# MusselGapeTracker_RevD.net
KiCad netlist of a schematic drawn in EAGLE
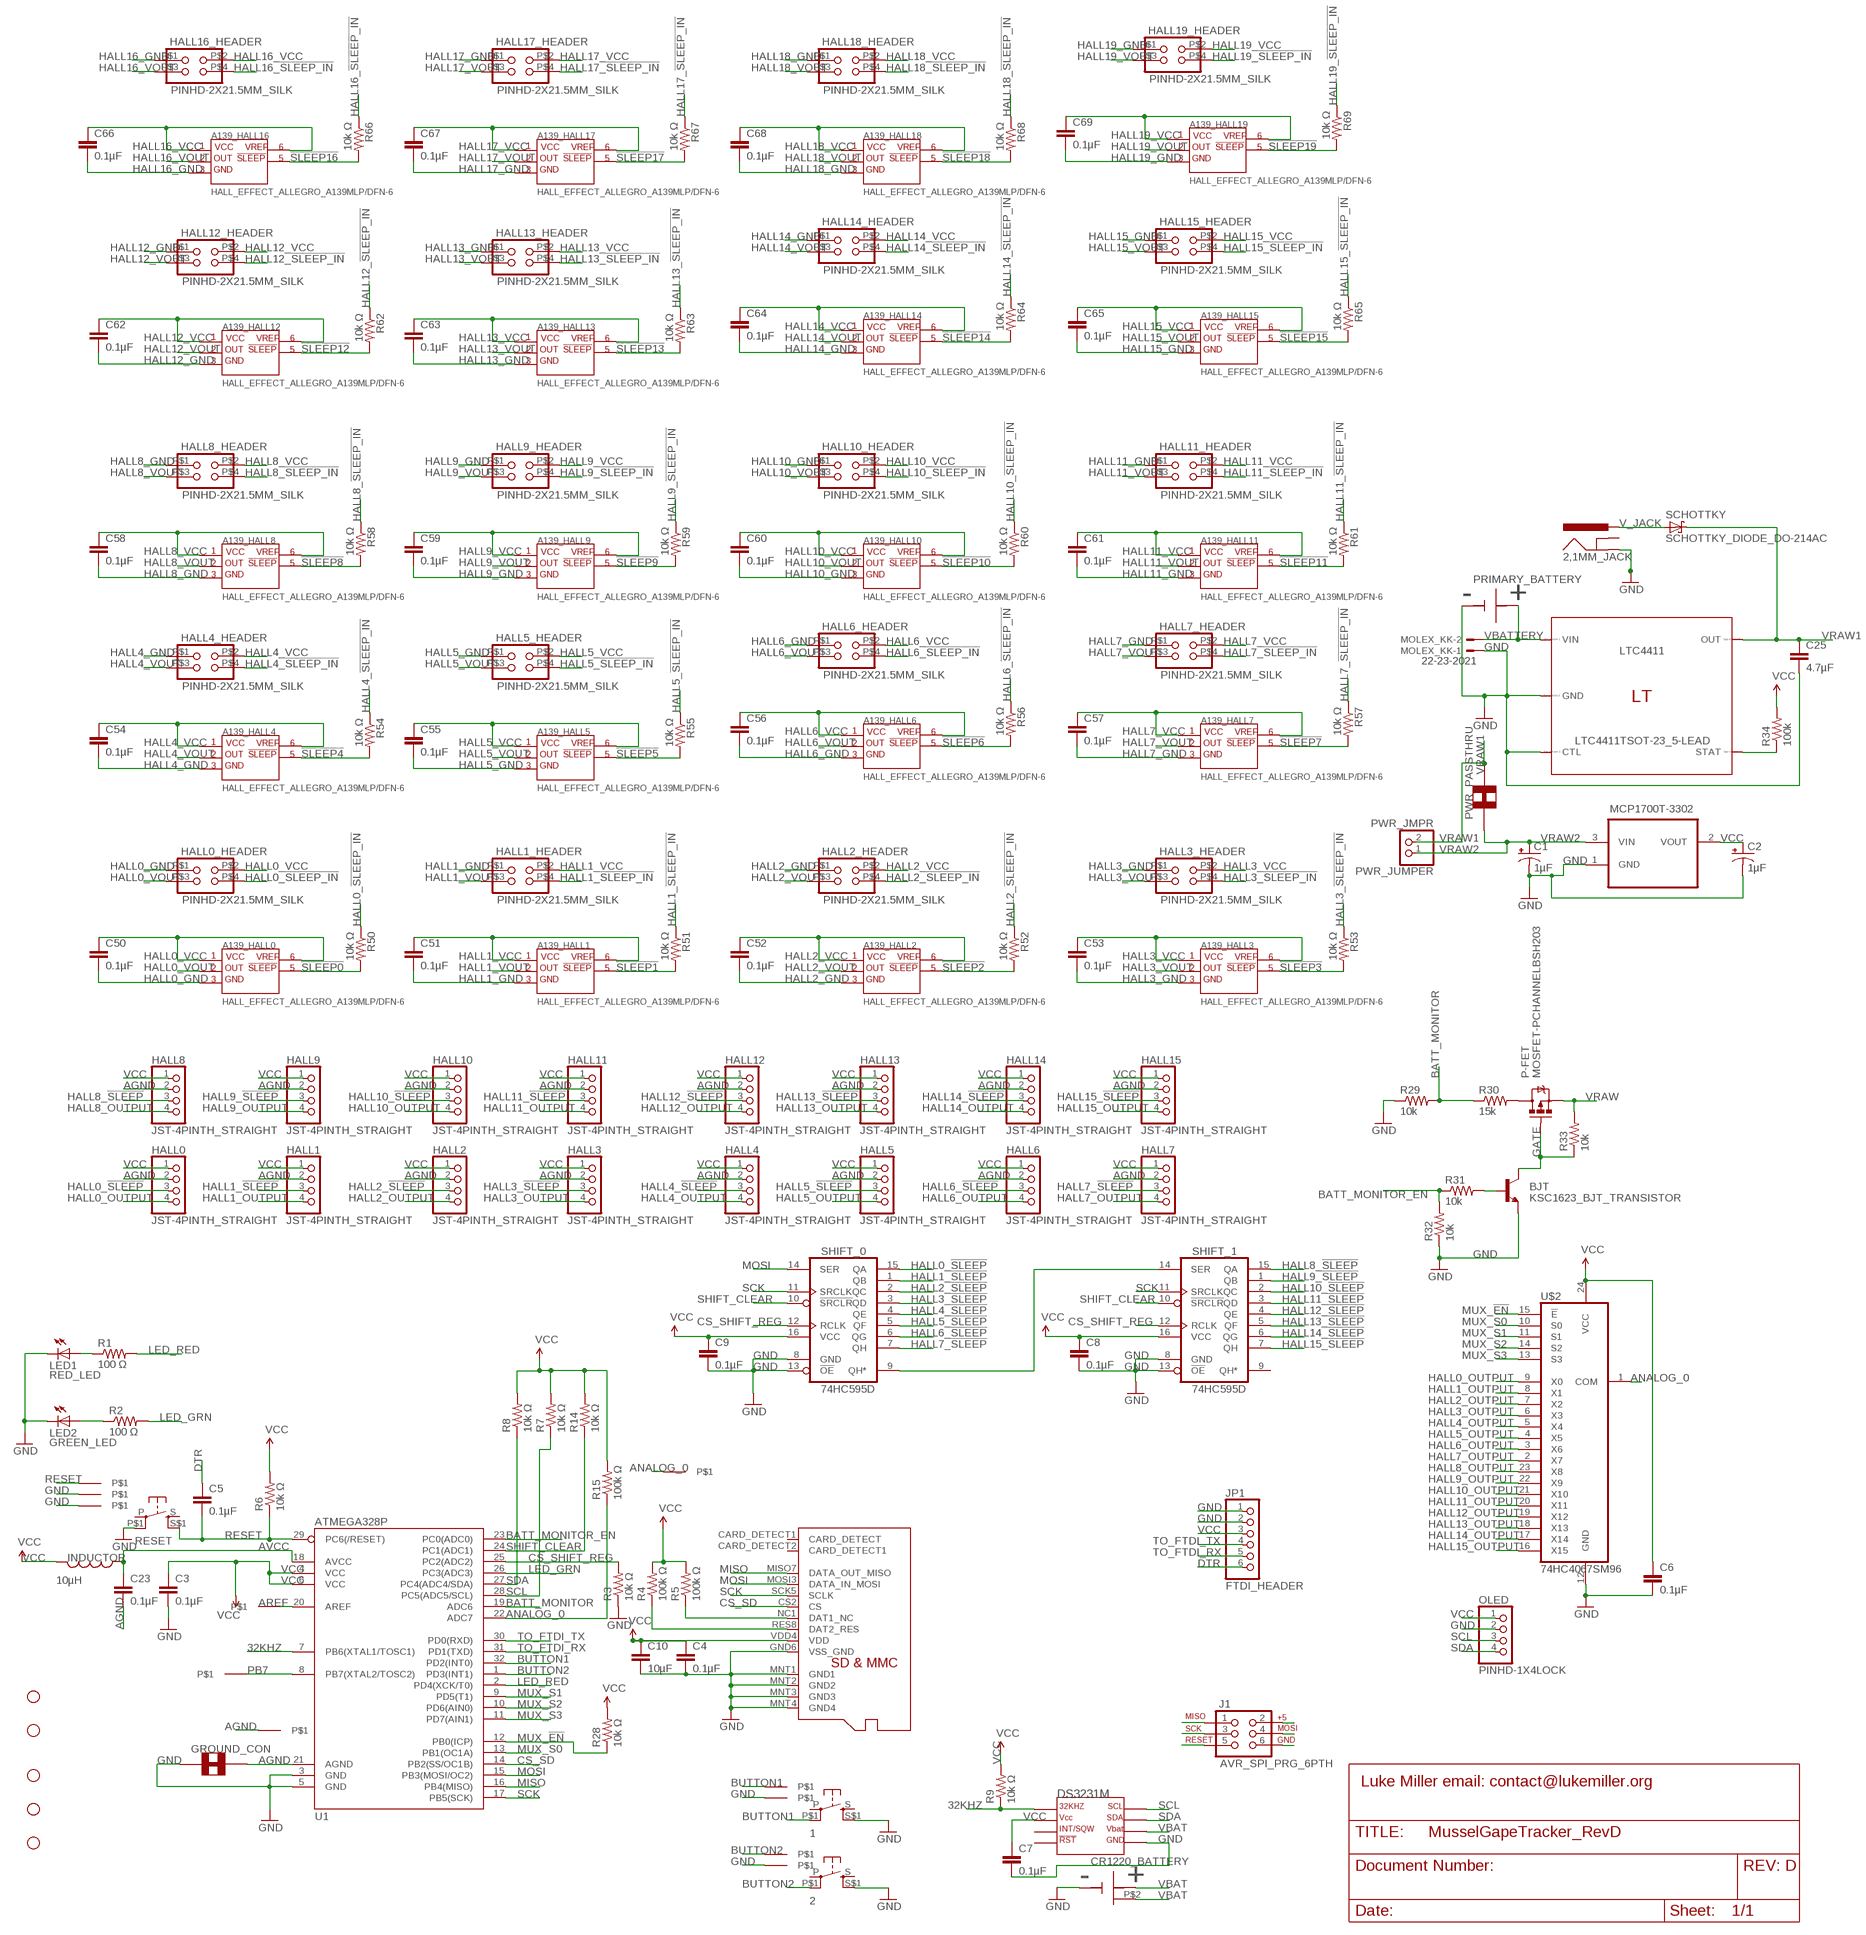
[diagram p0: schematic, sheet 1]

(export (version "E")
  (design (tool "Eeschema 10.0.6"))
  (components
    (comp (ref "1")
      (value "PUSHBUTTON_DPST_SMDSTANDARD")
      (footprint "eagle-import:PUSHBUTTON_DPST_SMD")
      (libsource (lib "eagle-import") (part "PUSHBUTTON_DPST_SMDSTANDARD"))
    )
    (comp (ref "2")
      (value "PUSHBUTTON_DPST_SMDSTANDARD")
      (footprint "eagle-import:PUSHBUTTON_DPST_SMD")
      (libsource (lib "eagle-import") (part "PUSHBUTTON_DPST_SMDSTANDARD"))
    )
    (comp (ref "2,1MM_JACK")
      (value "POWER_JACK_2,1MM")
      (footprint "eagle-import:POWER_JACK_DC_2,1MM")
      (libsource (lib "eagle-import") (part "POWER_JACK_2,1MM"))
    )
    (comp (ref "A139_HALL0")
      (value "HALL_EFFECT_ALLEGRO_A139MLP/DFN-6")
      (footprint "eagle-import:A139__HALL_EFFECT")
      (libsource (lib "eagle-import") (part "HALL_EFFECT_ALLEGRO_A139MLP/DFN-6"))
    )
    (comp (ref "A139_HALL1")
      (value "HALL_EFFECT_ALLEGRO_A139MLP/DFN-6")
      (footprint "eagle-import:A139__HALL_EFFECT")
      (libsource (lib "eagle-import") (part "HALL_EFFECT_ALLEGRO_A139MLP/DFN-6"))
    )
    (comp (ref "A139_HALL2")
      (value "HALL_EFFECT_ALLEGRO_A139MLP/DFN-6")
      (footprint "eagle-import:A139__HALL_EFFECT")
      (libsource (lib "eagle-import") (part "HALL_EFFECT_ALLEGRO_A139MLP/DFN-6"))
    )
    (comp (ref "A139_HALL3")
      (value "HALL_EFFECT_ALLEGRO_A139MLP/DFN-6")
      (footprint "eagle-import:A139__HALL_EFFECT")
      (libsource (lib "eagle-import") (part "HALL_EFFECT_ALLEGRO_A139MLP/DFN-6"))
    )
    (comp (ref "A139_HALL4")
      (value "HALL_EFFECT_ALLEGRO_A139MLP/DFN-6")
      (footprint "eagle-import:A139__HALL_EFFECT")
      (libsource (lib "eagle-import") (part "HALL_EFFECT_ALLEGRO_A139MLP/DFN-6"))
    )
    (comp (ref "A139_HALL5")
      (value "HALL_EFFECT_ALLEGRO_A139MLP/DFN-6")
      (footprint "eagle-import:A139__HALL_EFFECT")
      (libsource (lib "eagle-import") (part "HALL_EFFECT_ALLEGRO_A139MLP/DFN-6"))
    )
    (comp (ref "A139_HALL6")
      (value "HALL_EFFECT_ALLEGRO_A139MLP/DFN-6")
      (footprint "eagle-import:A139__HALL_EFFECT")
      (libsource (lib "eagle-import") (part "HALL_EFFECT_ALLEGRO_A139MLP/DFN-6"))
    )
    (comp (ref "A139_HALL7")
      (value "HALL_EFFECT_ALLEGRO_A139MLP/DFN-6")
      (footprint "eagle-import:A139__HALL_EFFECT")
      (libsource (lib "eagle-import") (part "HALL_EFFECT_ALLEGRO_A139MLP/DFN-6"))
    )
    (comp (ref "A139_HALL8")
      (value "HALL_EFFECT_ALLEGRO_A139MLP/DFN-6")
      (footprint "eagle-import:A139__HALL_EFFECT")
      (libsource (lib "eagle-import") (part "HALL_EFFECT_ALLEGRO_A139MLP/DFN-6"))
    )
    (comp (ref "A139_HALL9")
      (value "HALL_EFFECT_ALLEGRO_A139MLP/DFN-6")
      (footprint "eagle-import:A139__HALL_EFFECT")
      (libsource (lib "eagle-import") (part "HALL_EFFECT_ALLEGRO_A139MLP/DFN-6"))
    )
    (comp (ref "A139_HALL10")
      (value "HALL_EFFECT_ALLEGRO_A139MLP/DFN-6")
      (footprint "eagle-import:A139__HALL_EFFECT")
      (libsource (lib "eagle-import") (part "HALL_EFFECT_ALLEGRO_A139MLP/DFN-6"))
    )
    (comp (ref "A139_HALL11")
      (value "HALL_EFFECT_ALLEGRO_A139MLP/DFN-6")
      (footprint "eagle-import:A139__HALL_EFFECT")
      (libsource (lib "eagle-import") (part "HALL_EFFECT_ALLEGRO_A139MLP/DFN-6"))
    )
    (comp (ref "A139_HALL12")
      (value "HALL_EFFECT_ALLEGRO_A139MLP/DFN-6")
      (footprint "eagle-import:A139__HALL_EFFECT")
      (libsource (lib "eagle-import") (part "HALL_EFFECT_ALLEGRO_A139MLP/DFN-6"))
    )
    (comp (ref "A139_HALL13")
      (value "HALL_EFFECT_ALLEGRO_A139MLP/DFN-6")
      (footprint "eagle-import:A139__HALL_EFFECT")
      (libsource (lib "eagle-import") (part "HALL_EFFECT_ALLEGRO_A139MLP/DFN-6"))
    )
    (comp (ref "A139_HALL14")
      (value "HALL_EFFECT_ALLEGRO_A139MLP/DFN-6")
      (footprint "eagle-import:A139__HALL_EFFECT")
      (libsource (lib "eagle-import") (part "HALL_EFFECT_ALLEGRO_A139MLP/DFN-6"))
    )
    (comp (ref "A139_HALL15")
      (value "HALL_EFFECT_ALLEGRO_A139MLP/DFN-6")
      (footprint "eagle-import:A139__HALL_EFFECT")
      (libsource (lib "eagle-import") (part "HALL_EFFECT_ALLEGRO_A139MLP/DFN-6"))
    )
    (comp (ref "A139_HALL16")
      (value "HALL_EFFECT_ALLEGRO_A139MLP/DFN-6")
      (footprint "eagle-import:A139__HALL_EFFECT")
      (libsource (lib "eagle-import") (part "HALL_EFFECT_ALLEGRO_A139MLP/DFN-6"))
    )
    (comp (ref "A139_HALL17")
      (value "HALL_EFFECT_ALLEGRO_A139MLP/DFN-6")
      (footprint "eagle-import:A139__HALL_EFFECT")
      (libsource (lib "eagle-import") (part "HALL_EFFECT_ALLEGRO_A139MLP/DFN-6"))
    )
    (comp (ref "A139_HALL18")
      (value "HALL_EFFECT_ALLEGRO_A139MLP/DFN-6")
      (footprint "eagle-import:A139__HALL_EFFECT")
      (libsource (lib "eagle-import") (part "HALL_EFFECT_ALLEGRO_A139MLP/DFN-6"))
    )
    (comp (ref "A139_HALL19")
      (value "HALL_EFFECT_ALLEGRO_A139MLP/DFN-6")
      (footprint "eagle-import:A139__HALL_EFFECT")
      (libsource (lib "eagle-import") (part "HALL_EFFECT_ALLEGRO_A139MLP/DFN-6"))
    )
    (comp (ref "BJT")
      (value "KSC1623_BJT_TRANSISTOR")
      (footprint "eagle-import:SOT23")
      (libsource (lib "eagle-import") (part "KSC1623_BJT_TRANSISTOR"))
    )
    (comp (ref "C1")
      (value "1µF")
      (footprint "eagle-import:PANASONIC_B")
      (libsource (lib "eagle-import") (part "CPOL-USB"))
    )
    (comp (ref "C2")
      (value "1µF")
      (footprint "eagle-import:PANASONIC_B")
      (libsource (lib "eagle-import") (part "CPOL-USB"))
    )
    (comp (ref "C3")
      (value "0.1µF")
      (footprint "eagle-import:0603")
      (libsource (lib "eagle-import") (part "CAP0603"))
    )
    (comp (ref "C4")
      (value "0.1µF")
      (footprint "eagle-import:0603")
      (libsource (lib "eagle-import") (part "CAP0603"))
    )
    (comp (ref "C5")
      (value "0.1µF")
      (footprint "eagle-import:0603")
      (libsource (lib "eagle-import") (part "CAP0603"))
    )
    (comp (ref "C6")
      (value "0.1µF")
      (footprint "eagle-import:0603")
      (libsource (lib "eagle-import") (part "CAP0603"))
    )
    (comp (ref "C7")
      (value "0.1µF")
      (footprint "eagle-import:0603")
      (libsource (lib "eagle-import") (part "CAP0603"))
    )
    (comp (ref "C8")
      (value "0.1µF")
      (footprint "eagle-import:0603")
      (libsource (lib "eagle-import") (part "CAP0603"))
    )
    (comp (ref "C9")
      (value "0.1µF")
      (footprint "eagle-import:0603")
      (libsource (lib "eagle-import") (part "CAP0603"))
    )
    (comp (ref "C10")
      (value "10µF")
      (footprint "eagle-import:0603")
      (libsource (lib "eagle-import") (part "CAP0603"))
    )
    (comp (ref "C23")
      (value "0.1µF")
      (footprint "eagle-import:0603")
      (libsource (lib "eagle-import") (part "CAP0603"))
    )
    (comp (ref "C25")
      (value "4.7µF")
      (footprint "eagle-import:0603")
      (libsource (lib "eagle-import") (part "CAP0603"))
    )
    (comp (ref "C50")
      (value "0.1µF")
      (footprint "eagle-import:0603")
      (libsource (lib "eagle-import") (part "CAP0603"))
    )
    (comp (ref "C51")
      (value "0.1µF")
      (footprint "eagle-import:0603")
      (libsource (lib "eagle-import") (part "CAP0603"))
    )
    (comp (ref "C52")
      (value "0.1µF")
      (footprint "eagle-import:0603")
      (libsource (lib "eagle-import") (part "CAP0603"))
    )
    (comp (ref "C53")
      (value "0.1µF")
      (footprint "eagle-import:0603")
      (libsource (lib "eagle-import") (part "CAP0603"))
    )
    (comp (ref "C54")
      (value "0.1µF")
      (footprint "eagle-import:0603")
      (libsource (lib "eagle-import") (part "CAP0603"))
    )
    (comp (ref "C55")
      (value "0.1µF")
      (footprint "eagle-import:0603")
      (libsource (lib "eagle-import") (part "CAP0603"))
    )
    (comp (ref "C56")
      (value "0.1µF")
      (footprint "eagle-import:0603")
      (libsource (lib "eagle-import") (part "CAP0603"))
    )
    (comp (ref "C57")
      (value "0.1µF")
      (footprint "eagle-import:0603")
      (libsource (lib "eagle-import") (part "CAP0603"))
    )
    (comp (ref "C58")
      (value "0.1µF")
      (footprint "eagle-import:0603")
      (libsource (lib "eagle-import") (part "CAP0603"))
    )
    (comp (ref "C59")
      (value "0.1µF")
      (footprint "eagle-import:0603")
      (libsource (lib "eagle-import") (part "CAP0603"))
    )
    (comp (ref "C60")
      (value "0.1µF")
      (footprint "eagle-import:0603")
      (libsource (lib "eagle-import") (part "CAP0603"))
    )
    (comp (ref "C61")
      (value "0.1µF")
      (footprint "eagle-import:0603")
      (libsource (lib "eagle-import") (part "CAP0603"))
    )
    (comp (ref "C62")
      (value "0.1µF")
      (footprint "eagle-import:0603")
      (libsource (lib "eagle-import") (part "CAP0603"))
    )
    (comp (ref "C63")
      (value "0.1µF")
      (footprint "eagle-import:0603")
      (libsource (lib "eagle-import") (part "CAP0603"))
    )
    (comp (ref "C64")
      (value "0.1µF")
      (footprint "eagle-import:0603")
      (libsource (lib "eagle-import") (part "CAP0603"))
    )
    (comp (ref "C65")
      (value "0.1µF")
      (footprint "eagle-import:0603")
      (libsource (lib "eagle-import") (part "CAP0603"))
    )
    (comp (ref "C66")
      (value "0.1µF")
      (footprint "eagle-import:0603")
      (libsource (lib "eagle-import") (part "CAP0603"))
    )
    (comp (ref "C67")
      (value "0.1µF")
      (footprint "eagle-import:0603")
      (libsource (lib "eagle-import") (part "CAP0603"))
    )
    (comp (ref "C68")
      (value "0.1µF")
      (footprint "eagle-import:0603")
      (libsource (lib "eagle-import") (part "CAP0603"))
    )
    (comp (ref "C69")
      (value "0.1µF")
      (footprint "eagle-import:0603")
      (libsource (lib "eagle-import") (part "CAP0603"))
    )
    (comp (ref "CR1220_BATTERY")
      (value "CR1220_BATTERY_HOLDERSMD")
      (footprint "eagle-import:CR1220_BATTERY_HOLDER_SMD")
      (libsource (lib "eagle-import") (part "CR1220_BATTERY_HOLDERSMD"))
    )
    (comp (ref "DS3231M")
      (value "DS3231MSOIC-8")
      (footprint "eagle-import:DS3231M_SOIC8")
      (libsource (lib "eagle-import") (part "DS3231MSOIC-8"))
    )
    (comp (ref "GND")
      (value "PINHD-1X1SMALL")
      (footprint "eagle-import:1X01_SMALL")
      (libsource (lib "eagle-import") (part "PINHD-1X1SMALL"))
    )
    (comp (ref "GROUND_CON")
      (value "SOLDER_JUMPER_TRACESTANDARD")
      (footprint "eagle-import:SJ_2S-TRACE")
      (libsource (lib "eagle-import") (part "SOLDER_JUMPER_TRACESTANDARD"))
    )
    (comp (ref "HALL0")
      (value "JST-4PINTH_STRAIGHT")
      (footprint "eagle-import:JST-PH-4-THM")
      (libsource (lib "eagle-import") (part "JST-4PINTH_STRAIGHT"))
    )
    (comp (ref "HALL0_HEADER")
      (value "PINHD-2X21.5MM_SILK")
      (footprint "eagle-import:2X2_1.5MM")
      (libsource (lib "eagle-import") (part "PINHD-2X21.5MM_SILK"))
    )
    (comp (ref "HALL1")
      (value "JST-4PINTH_STRAIGHT")
      (footprint "eagle-import:JST-PH-4-THM")
      (libsource (lib "eagle-import") (part "JST-4PINTH_STRAIGHT"))
    )
    (comp (ref "HALL1_HEADER")
      (value "PINHD-2X21.5MM_SILK")
      (footprint "eagle-import:2X2_1.5MM")
      (libsource (lib "eagle-import") (part "PINHD-2X21.5MM_SILK"))
    )
    (comp (ref "HALL2")
      (value "JST-4PINTH_STRAIGHT")
      (footprint "eagle-import:JST-PH-4-THM")
      (libsource (lib "eagle-import") (part "JST-4PINTH_STRAIGHT"))
    )
    (comp (ref "HALL2_HEADER")
      (value "PINHD-2X21.5MM_SILK")
      (footprint "eagle-import:2X2_1.5MM")
      (libsource (lib "eagle-import") (part "PINHD-2X21.5MM_SILK"))
    )
    (comp (ref "HALL3")
      (value "JST-4PINTH_STRAIGHT")
      (footprint "eagle-import:JST-PH-4-THM")
      (libsource (lib "eagle-import") (part "JST-4PINTH_STRAIGHT"))
    )
    (comp (ref "HALL3_HEADER")
      (value "PINHD-2X21.5MM_SILK")
      (footprint "eagle-import:2X2_1.5MM")
      (libsource (lib "eagle-import") (part "PINHD-2X21.5MM_SILK"))
    )
    (comp (ref "HALL4")
      (value "JST-4PINTH_STRAIGHT")
      (footprint "eagle-import:JST-PH-4-THM")
      (libsource (lib "eagle-import") (part "JST-4PINTH_STRAIGHT"))
    )
    (comp (ref "HALL4_HEADER")
      (value "PINHD-2X21.5MM_SILK")
      (footprint "eagle-import:2X2_1.5MM")
      (libsource (lib "eagle-import") (part "PINHD-2X21.5MM_SILK"))
    )
    (comp (ref "HALL5")
      (value "JST-4PINTH_STRAIGHT")
      (footprint "eagle-import:JST-PH-4-THM")
      (libsource (lib "eagle-import") (part "JST-4PINTH_STRAIGHT"))
    )
    (comp (ref "HALL5_HEADER")
      (value "PINHD-2X21.5MM_SILK")
      (footprint "eagle-import:2X2_1.5MM")
      (libsource (lib "eagle-import") (part "PINHD-2X21.5MM_SILK"))
    )
    (comp (ref "HALL6")
      (value "JST-4PINTH_STRAIGHT")
      (footprint "eagle-import:JST-PH-4-THM")
      (libsource (lib "eagle-import") (part "JST-4PINTH_STRAIGHT"))
    )
    (comp (ref "HALL6_HEADER")
      (value "PINHD-2X21.5MM_SILK")
      (footprint "eagle-import:2X2_1.5MM")
      (libsource (lib "eagle-import") (part "PINHD-2X21.5MM_SILK"))
    )
    (comp (ref "HALL7")
      (value "JST-4PINTH_STRAIGHT")
      (footprint "eagle-import:JST-PH-4-THM")
      (libsource (lib "eagle-import") (part "JST-4PINTH_STRAIGHT"))
    )
    (comp (ref "HALL7_HEADER")
      (value "PINHD-2X21.5MM_SILK")
      (footprint "eagle-import:2X2_1.5MM")
      (libsource (lib "eagle-import") (part "PINHD-2X21.5MM_SILK"))
    )
    (comp (ref "HALL8")
      (value "JST-4PINTH_STRAIGHT")
      (footprint "eagle-import:JST-PH-4-THM")
      (libsource (lib "eagle-import") (part "JST-4PINTH_STRAIGHT"))
    )
    (comp (ref "HALL8_HEADER")
      (value "PINHD-2X21.5MM_SILK")
      (footprint "eagle-import:2X2_1.5MM")
      (libsource (lib "eagle-import") (part "PINHD-2X21.5MM_SILK"))
    )
    (comp (ref "HALL9")
      (value "JST-4PINTH_STRAIGHT")
      (footprint "eagle-import:JST-PH-4-THM")
      (libsource (lib "eagle-import") (part "JST-4PINTH_STRAIGHT"))
    )
    (comp (ref "HALL9_HEADER")
      (value "PINHD-2X21.5MM_SILK")
      (footprint "eagle-import:2X2_1.5MM")
      (libsource (lib "eagle-import") (part "PINHD-2X21.5MM_SILK"))
    )
    (comp (ref "HALL10")
      (value "JST-4PINTH_STRAIGHT")
      (footprint "eagle-import:JST-PH-4-THM")
      (libsource (lib "eagle-import") (part "JST-4PINTH_STRAIGHT"))
    )
    (comp (ref "HALL10_HEADER")
      (value "PINHD-2X21.5MM_SILK")
      (footprint "eagle-import:2X2_1.5MM")
      (libsource (lib "eagle-import") (part "PINHD-2X21.5MM_SILK"))
    )
    (comp (ref "HALL11")
      (value "JST-4PINTH_STRAIGHT")
      (footprint "eagle-import:JST-PH-4-THM")
      (libsource (lib "eagle-import") (part "JST-4PINTH_STRAIGHT"))
    )
    (comp (ref "HALL11_HEADER")
      (value "PINHD-2X21.5MM_SILK")
      (footprint "eagle-import:2X2_1.5MM")
      (libsource (lib "eagle-import") (part "PINHD-2X21.5MM_SILK"))
    )
    (comp (ref "HALL12")
      (value "JST-4PINTH_STRAIGHT")
      (footprint "eagle-import:JST-PH-4-THM")
      (libsource (lib "eagle-import") (part "JST-4PINTH_STRAIGHT"))
    )
    (comp (ref "HALL12_HEADER")
      (value "PINHD-2X21.5MM_SILK")
      (footprint "eagle-import:2X2_1.5MM")
      (libsource (lib "eagle-import") (part "PINHD-2X21.5MM_SILK"))
    )
    (comp (ref "HALL13")
      (value "JST-4PINTH_STRAIGHT")
      (footprint "eagle-import:JST-PH-4-THM")
      (libsource (lib "eagle-import") (part "JST-4PINTH_STRAIGHT"))
    )
    (comp (ref "HALL13_HEADER")
      (value "PINHD-2X21.5MM_SILK")
      (footprint "eagle-import:2X2_1.5MM")
      (libsource (lib "eagle-import") (part "PINHD-2X21.5MM_SILK"))
    )
    (comp (ref "HALL14")
      (value "JST-4PINTH_STRAIGHT")
      (footprint "eagle-import:JST-PH-4-THM")
      (libsource (lib "eagle-import") (part "JST-4PINTH_STRAIGHT"))
    )
    (comp (ref "HALL14_HEADER")
      (value "PINHD-2X21.5MM_SILK")
      (footprint "eagle-import:2X2_1.5MM")
      (libsource (lib "eagle-import") (part "PINHD-2X21.5MM_SILK"))
    )
    (comp (ref "HALL15")
      (value "JST-4PINTH_STRAIGHT")
      (footprint "eagle-import:JST-PH-4-THM")
      (libsource (lib "eagle-import") (part "JST-4PINTH_STRAIGHT"))
    )
    (comp (ref "HALL15_HEADER")
      (value "PINHD-2X21.5MM_SILK")
      (footprint "eagle-import:2X2_1.5MM")
      (libsource (lib "eagle-import") (part "PINHD-2X21.5MM_SILK"))
    )
    (comp (ref "HALL16_HEADER")
      (value "PINHD-2X21.5MM_SILK")
      (footprint "eagle-import:2X2_1.5MM")
      (libsource (lib "eagle-import") (part "PINHD-2X21.5MM_SILK"))
    )
    (comp (ref "HALL17_HEADER")
      (value "PINHD-2X21.5MM_SILK")
      (footprint "eagle-import:2X2_1.5MM")
      (libsource (lib "eagle-import") (part "PINHD-2X21.5MM_SILK"))
    )
    (comp (ref "HALL18_HEADER")
      (value "PINHD-2X21.5MM_SILK")
      (footprint "eagle-import:2X2_1.5MM")
      (libsource (lib "eagle-import") (part "PINHD-2X21.5MM_SILK"))
    )
    (comp (ref "HALL19_HEADER")
      (value "PINHD-2X21.5MM_SILK")
      (footprint "eagle-import:2X2_1.5MM")
      (libsource (lib "eagle-import") (part "PINHD-2X21.5MM_SILK"))
    )
    (comp (ref "INDUCTOR")
      (value "10µH")
      (footprint "eagle-import:I_0805")
      (libsource (lib "eagle-import") (part "INDUCTOR0805_TY"))
    )
    (comp (ref "J1")
      (value "AVR_SPI_PRG_6PTH")
      (footprint "eagle-import:2X3")
      (libsource (lib "eagle-import") (part "AVR_SPI_PRG_6PTH"))
    )
    (comp (ref "JP1")
      (value "FTDI_HEADER")
      (footprint "eagle-import:1X06-RIGHT_ANGLE")
      (libsource (lib "eagle-import") (part "PINHD-1X6RA"))
    )
    (comp (ref "LED1")
      (value "RED_LED")
      (footprint "eagle-import:CHIPLED_0805")
      (libsource (lib "eagle-import") (part "LED0805"))
    )
    (comp (ref "LED2")
      (value "GREEN_LED")
      (footprint "eagle-import:CHIPLED_0805")
      (libsource (lib "eagle-import") (part "LED0805"))
    )
    (comp (ref "LTC4411")
      (value "LTC4411TSOT-23_5-LEAD")
      (footprint "eagle-import:TSOT-23_5-LEAD")
      (libsource (lib "eagle-import") (part "LTC4411TSOT-23_5-LEAD"))
    )
    (comp (ref "MCP1700T-3302")
      (value "MCP1700T-3302E/TT")
      (footprint "eagle-import:SOT95P237X112-3N")
      (libsource (lib "eagle-import") (part "MCP1700T-3302E/TT"))
    )
    (comp (ref "MOLEX_KK")
      (value "22-23-2021")
      (footprint "eagle-import:22-23-2021")
      (fields (field (name "MF") "MOLEX"))
      (libsource (lib "eagle-import") (part "22-23-2021"))
    )
    (comp (ref "OLED")
      (value "PINHD-1X4LOCK")
      (footprint "eagle-import:1X04_LOCK")
      (libsource (lib "eagle-import") (part "PINHD-1X4LOCK"))
    )
    (comp (ref "P-FET")
      (value "MOSFET-PCHANNELBSH203")
      (footprint "eagle-import:SOT23-3")
      (libsource (lib "eagle-import") (part "MOSFET-PCHANNELBSH203"))
    )
    (comp (ref "PB7")
      (value "PINHD-1X1SMALL")
      (footprint "eagle-import:1X01_SMALL")
      (libsource (lib "eagle-import") (part "PINHD-1X1SMALL"))
    )
    (comp (ref "PRIMARY_BATTERY")
      (value "BATTERY_4XAA")
      (footprint "eagle-import:BATTERY_4XAA_PTH")
      (libsource (lib "eagle-import") (part "BATTERY_4XAA"))
    )
    (comp (ref "PWR_JUMPER")
      (value "PWR_JMPR")
      (footprint "eagle-import:1X02_NOSILK")
      (libsource (lib "eagle-import") (part "PINHD-1X2NOSILK"))
    )
    (comp (ref "PWR_PASSTHRU")
      (value "PWR")
      (footprint "eagle-import:SJ_2S-TRACE")
      (libsource (lib "eagle-import") (part "SOLDER_JUMPER_TRACESTANDARD"))
    )
    (comp (ref "R1")
      (value "100 Ω")
      (footprint "eagle-import:R0603")
      (libsource (lib "eagle-import") (part "RESISTOR_SMDR0603"))
    )
    (comp (ref "R2")
      (value "100 Ω")
      (footprint "eagle-import:R0603")
      (libsource (lib "eagle-import") (part "RESISTOR_SMDR0603"))
    )
    (comp (ref "R3")
      (value "10k Ω")
      (footprint "eagle-import:R0603")
      (libsource (lib "eagle-import") (part "RESISTOR_SMDR0603"))
    )
    (comp (ref "R4")
      (value "100k Ω")
      (footprint "eagle-import:R0603")
      (libsource (lib "eagle-import") (part "RESISTOR_SMDR0603"))
    )
    (comp (ref "R5")
      (value "100k Ω")
      (footprint "eagle-import:R0603")
      (libsource (lib "eagle-import") (part "RESISTOR_SMDR0603"))
    )
    (comp (ref "R6")
      (value "10k Ω")
      (footprint "eagle-import:R0603")
      (libsource (lib "eagle-import") (part "RESISTOR_SMDR0603"))
    )
    (comp (ref "R7")
      (value "10k Ω")
      (footprint "eagle-import:R0603")
      (libsource (lib "eagle-import") (part "RESISTOR_SMDR0603"))
    )
    (comp (ref "R8")
      (value "10k Ω")
      (footprint "eagle-import:R0603")
      (libsource (lib "eagle-import") (part "RESISTOR_SMDR0603"))
    )
    (comp (ref "R9")
      (value "10k Ω")
      (footprint "eagle-import:R0603")
      (libsource (lib "eagle-import") (part "RESISTOR_SMDR0603"))
    )
    (comp (ref "R14")
      (value "10k Ω")
      (footprint "eagle-import:R0603")
      (libsource (lib "eagle-import") (part "RESISTOR_SMDR0603"))
    )
    (comp (ref "R15")
      (value "100k Ω")
      (footprint "eagle-import:R0603")
      (libsource (lib "eagle-import") (part "RESISTOR_SMDR0603"))
    )
    (comp (ref "R28")
      (value "10k Ω")
      (footprint "eagle-import:R0603")
      (libsource (lib "eagle-import") (part "RESISTOR_SMDR0603"))
    )
    (comp (ref "R29")
      (value "10k")
      (footprint "eagle-import:R0603")
      (libsource (lib "eagle-import") (part "RESISTOR_SMDR0603"))
    )
    (comp (ref "R30")
      (value "15k")
      (footprint "eagle-import:R0603")
      (libsource (lib "eagle-import") (part "RESISTOR_SMDR0603"))
    )
    (comp (ref "R31")
      (value "10k")
      (footprint "eagle-import:R0603")
      (libsource (lib "eagle-import") (part "RESISTOR_SMDR0603"))
    )
    (comp (ref "R32")
      (value "10k")
      (footprint "eagle-import:R0603")
      (libsource (lib "eagle-import") (part "RESISTOR_SMDR0603"))
    )
    (comp (ref "R33")
      (value "10k")
      (footprint "eagle-import:R0603")
      (libsource (lib "eagle-import") (part "RESISTOR_SMDR0603"))
    )
    (comp (ref "R34")
      (value "100k")
      (footprint "eagle-import:R0603")
      (libsource (lib "eagle-import") (part "RESISTOR_SMDR0603"))
    )
    (comp (ref "R50")
      (value "10k Ω")
      (footprint "eagle-import:R0603")
      (libsource (lib "eagle-import") (part "RESISTOR_SMDR0603"))
    )
    (comp (ref "R51")
      (value "10k Ω")
      (footprint "eagle-import:R0603")
      (libsource (lib "eagle-import") (part "RESISTOR_SMDR0603"))
    )
    (comp (ref "R52")
      (value "10k Ω")
      (footprint "eagle-import:R0603")
      (libsource (lib "eagle-import") (part "RESISTOR_SMDR0603"))
    )
    (comp (ref "R53")
      (value "10k Ω")
      (footprint "eagle-import:R0603")
      (libsource (lib "eagle-import") (part "RESISTOR_SMDR0603"))
    )
    (comp (ref "R54")
      (value "10k Ω")
      (footprint "eagle-import:R0603")
      (libsource (lib "eagle-import") (part "RESISTOR_SMDR0603"))
    )
    (comp (ref "R55")
      (value "10k Ω")
      (footprint "eagle-import:R0603")
      (libsource (lib "eagle-import") (part "RESISTOR_SMDR0603"))
    )
    (comp (ref "R56")
      (value "10k Ω")
      (footprint "eagle-import:R0603")
      (libsource (lib "eagle-import") (part "RESISTOR_SMDR0603"))
    )
    (comp (ref "R57")
      (value "10k Ω")
      (footprint "eagle-import:R0603")
      (libsource (lib "eagle-import") (part "RESISTOR_SMDR0603"))
    )
    (comp (ref "R58")
      (value "10k Ω")
      (footprint "eagle-import:R0603")
      (libsource (lib "eagle-import") (part "RESISTOR_SMDR0603"))
    )
    (comp (ref "R59")
      (value "10k Ω")
      (footprint "eagle-import:R0603")
      (libsource (lib "eagle-import") (part "RESISTOR_SMDR0603"))
    )
    (comp (ref "R60")
      (value "10k Ω")
      (footprint "eagle-import:R0603")
      (libsource (lib "eagle-import") (part "RESISTOR_SMDR0603"))
    )
    (comp (ref "R61")
      (value "10k Ω")
      (footprint "eagle-import:R0603")
      (libsource (lib "eagle-import") (part "RESISTOR_SMDR0603"))
    )
    (comp (ref "R62")
      (value "10k Ω")
      (footprint "eagle-import:R0603")
      (libsource (lib "eagle-import") (part "RESISTOR_SMDR0603"))
    )
    (comp (ref "R63")
      (value "10k Ω")
      (footprint "eagle-import:R0603")
      (libsource (lib "eagle-import") (part "RESISTOR_SMDR0603"))
    )
    (comp (ref "R64")
      (value "10k Ω")
      (footprint "eagle-import:R0603")
      (libsource (lib "eagle-import") (part "RESISTOR_SMDR0603"))
    )
    (comp (ref "R65")
      (value "10k Ω")
      (footprint "eagle-import:R0603")
      (libsource (lib "eagle-import") (part "RESISTOR_SMDR0603"))
    )
    (comp (ref "R66")
      (value "10k Ω")
      (footprint "eagle-import:R0603")
      (libsource (lib "eagle-import") (part "RESISTOR_SMDR0603"))
    )
    (comp (ref "R67")
      (value "10k Ω")
      (footprint "eagle-import:R0603")
      (libsource (lib "eagle-import") (part "RESISTOR_SMDR0603"))
    )
    (comp (ref "R68")
      (value "10k Ω")
      (footprint "eagle-import:R0603")
      (libsource (lib "eagle-import") (part "RESISTOR_SMDR0603"))
    )
    (comp (ref "R69")
      (value "10k Ω")
      (footprint "eagle-import:R0603")
      (libsource (lib "eagle-import") (part "RESISTOR_SMDR0603"))
    )
    (comp (ref "RESET")
      (value "PUSHBUTTON_DPST_SMDSTANDARD")
      (footprint "eagle-import:PUSHBUTTON_DPST_SMD")
      (libsource (lib "eagle-import") (part "PUSHBUTTON_DPST_SMDSTANDARD"))
    )
    (comp (ref "SCHOTTKY")
      (value "SCHOTTKY_DIODE_DO-214AC")
      (footprint "eagle-import:DO214AC")
      (libsource (lib "eagle-import") (part "SCHOTTKY_DIODE_DO-214AC"))
    )
    (comp (ref "SHIFT_0")
      (value "74HC595D")
      (footprint "eagle-import:SO16")
      (libsource (lib "eagle-import") (part "74HC595D"))
    )
    (comp (ref "SHIFT_1")
      (value "74HC595D")
      (footprint "eagle-import:SO16")
      (libsource (lib "eagle-import") (part "74HC595D"))
    )
    (comp (ref "STANDOFF1")
      (value "STAND-OFF4-40")
      (footprint "eagle-import:STAND-OFF")
      (libsource (lib "eagle-import") (part "STAND-OFF4-40"))
    )
    (comp (ref "STANDOFF2")
      (value "STAND-OFF4-40")
      (footprint "eagle-import:STAND-OFF")
      (libsource (lib "eagle-import") (part "STAND-OFF4-40"))
    )
    (comp (ref "STANDOFF3")
      (value "STAND-OFF4-40")
      (footprint "eagle-import:STAND-OFF")
      (libsource (lib "eagle-import") (part "STAND-OFF4-40"))
    )
    (comp (ref "STANDOFF4_M2")
      (value "STAND-OFFM2")
      (footprint "eagle-import:STAND-OFF_M2")
      (libsource (lib "eagle-import") (part "STAND-OFFM2"))
    )
    (comp (ref "STANDOFF5_M2")
      (value "STAND-OFFM2")
      (footprint "eagle-import:STAND-OFF_M2")
      (libsource (lib "eagle-import") (part "STAND-OFFM2"))
    )
    (comp (ref "U$1")
      (value "MICROSD_MOLEX_REVERSECURRENT")
      (footprint "eagle-import:MICROSD_SOCKET_MOLEX_REVERSEMOUNT")
      (libsource (lib "eagle-import") (part "MICROSD_MOLEX_REVERSECURRENT"))
    )
    (comp (ref "U$2")
      (value "74HC4067SM96")
      (footprint "eagle-import:SSOP24")
      (libsource (lib "eagle-import") (part "74HC4067SM96"))
    )
    (comp (ref "U$3")
      (value "PINHD-1X1SMALL")
      (footprint "eagle-import:1X01_SMALL")
      (libsource (lib "eagle-import") (part "PINHD-1X1SMALL"))
    )
    (comp (ref "U$4")
      (value "PINHD-1X1SMALL")
      (footprint "eagle-import:1X01_SMALL")
      (libsource (lib "eagle-import") (part "PINHD-1X1SMALL"))
    )
    (comp (ref "U$6")
      (value "PINHD-1X1SMALL")
      (footprint "eagle-import:1X01_SMALL")
      (libsource (lib "eagle-import") (part "PINHD-1X1SMALL"))
    )
    (comp (ref "U$7")
      (value "PINHD-1X1SMALL")
      (footprint "eagle-import:1X01_SMALL")
      (libsource (lib "eagle-import") (part "PINHD-1X1SMALL"))
    )
    (comp (ref "U$8")
      (value "PINHD-1X1SMALL")
      (footprint "eagle-import:1X01_SMALL")
      (libsource (lib "eagle-import") (part "PINHD-1X1SMALL"))
    )
    (comp (ref "U$9")
      (value "PINHD-1X1SMALL")
      (footprint "eagle-import:1X01_SMALL")
      (libsource (lib "eagle-import") (part "PINHD-1X1SMALL"))
    )
    (comp (ref "U$10")
      (value "PINHD-1X1SMALL")
      (footprint "eagle-import:1X01_SMALL")
      (libsource (lib "eagle-import") (part "PINHD-1X1SMALL"))
    )
    (comp (ref "U$11")
      (value "PINHD-1X1SMALL")
      (footprint "eagle-import:1X01_SMALL")
      (libsource (lib "eagle-import") (part "PINHD-1X1SMALL"))
    )
    (comp (ref "U$17")
      (value "PINHD-1X1SMALL")
      (footprint "eagle-import:1X01_SMALL")
      (libsource (lib "eagle-import") (part "PINHD-1X1SMALL"))
    )
    (comp (ref "U1")
      (value "ATMEGA328P")
      (footprint "eagle-import:TQFP32-08")
      (libsource (lib "eagle-import") (part "ATMEGA328_SMT"))
    )
  )
  (nets
    (net (code "1") (name "/32KHZ") (class "Default")
      (node (ref "DS3231M") (pin "1") (pinfunction "P$1_32KHZ_1") (pintype "bidirectional"))
      (node (ref "R9") (pin "1") (pinfunction "1_1") (pintype "passive"))
      (node (ref "U1") (pin "7") (pinfunction "PB6(XTAL1/TOSC1)_7") (pintype "bidirectional"))
    )
    (net (code "2") (name "/AGND") (class "Default")
      (node (ref "C23") (pin "2") (pinfunction "2_2") (pintype "passive"))
      (node (ref "GROUND_CON") (pin "2") (pinfunction "P$2_2") (pintype "bidirectional"))
      (node (ref "HALL0") (pin "2") (pinfunction "2_2") (pintype "passive"))
      (node (ref "HALL1") (pin "2") (pinfunction "2_2") (pintype "passive"))
      (node (ref "HALL10") (pin "2") (pinfunction "2_2") (pintype "passive"))
      (node (ref "HALL11") (pin "2") (pinfunction "2_2") (pintype "passive"))
      (node (ref "HALL12") (pin "2") (pinfunction "2_2") (pintype "passive"))
      (node (ref "HALL13") (pin "2") (pinfunction "2_2") (pintype "passive"))
      (node (ref "HALL14") (pin "2") (pinfunction "2_2") (pintype "passive"))
      (node (ref "HALL15") (pin "2") (pinfunction "2_2") (pintype "passive"))
      (node (ref "HALL2") (pin "2") (pinfunction "2_2") (pintype "passive"))
      (node (ref "HALL3") (pin "2") (pinfunction "2_2") (pintype "passive"))
      (node (ref "HALL4") (pin "2") (pinfunction "2_2") (pintype "passive"))
      (node (ref "HALL5") (pin "2") (pinfunction "2_2") (pintype "passive"))
      (node (ref "HALL6") (pin "2") (pinfunction "2_2") (pintype "passive"))
      (node (ref "HALL7") (pin "2") (pinfunction "2_2") (pintype "passive"))
      (node (ref "HALL8") (pin "2") (pinfunction "2_2") (pintype "passive"))
      (node (ref "HALL9") (pin "2") (pinfunction "2_2") (pintype "passive"))
      (node (ref "U$11") (pin "1") (pinfunction "P$1_1") (pintype "bidirectional"))
      (node (ref "U1") (pin "21") (pinfunction "AGND_21") (pintype "bidirectional"))
    )
    (net (code "3") (name "/ANALOG_0") (class "Default")
      (node (ref "R15") (pin "1") (pinfunction "1_1") (pintype "passive"))
      (node (ref "U$10") (pin "1") (pinfunction "P$1_1") (pintype "bidirectional"))
      (node (ref "U$2") (pin "1") (pinfunction "COM_1") (pintype "output"))
      (node (ref "U1") (pin "22") (pinfunction "ADC7_22") (pintype "bidirectional"))
    )
    (net (code "4") (name "/AREF") (class "Default")
      (node (ref "U$17") (pin "1") (pinfunction "P$1_1") (pintype "bidirectional"))
      (node (ref "U1") (pin "20") (pinfunction "AREF_20") (pintype "bidirectional"))
    )
    (net (code "5") (name "/AVCC") (class "Default")
      (node (ref "C23") (pin "1") (pinfunction "1_1") (pintype "passive"))
      (node (ref "INDUCTOR") (pin "P$1") (pinfunction "1_P$1") (pintype "passive"))
      (node (ref "U1") (pin "18") (pinfunction "AVCC_18") (pintype "bidirectional"))
    )
    (net (code "6") (name "/BATT_MONITOR") (class "Default")
      (node (ref "R29") (pin "2") (pinfunction "2_2") (pintype "passive"))
      (node (ref "R30") (pin "1") (pinfunction "1_1") (pintype "passive"))
      (node (ref "U1") (pin "19") (pinfunction "ADC6_19") (pintype "bidirectional"))
    )
    (net (code "7") (name "/BATT_MONITOR_EN") (class "Default")
      (node (ref "R31") (pin "1") (pinfunction "1_1") (pintype "passive"))
      (node (ref "R32") (pin "2") (pinfunction "2_2") (pintype "passive"))
      (node (ref "U1") (pin "23") (pinfunction "PC0(ADC0)_23") (pintype "bidirectional"))
    )
    (net (code "8") (name "/BUTTON1") (class "Default")
      (node (ref "1") (pin "P$1") (pinfunction "P1_P$1") (pintype "passive"))
      (node (ref "U$6") (pin "1") (pinfunction "P$1_1") (pintype "bidirectional"))
      (node (ref "U1") (pin "32") (pinfunction "PD2(INT0)_32") (pintype "bidirectional"))
    )
    (net (code "9") (name "/BUTTON2") (class "Default")
      (node (ref "2") (pin "P$1") (pinfunction "P1_P$1") (pintype "passive"))
      (node (ref "U$8") (pin "1") (pinfunction "P$1_1") (pintype "bidirectional"))
      (node (ref "U1") (pin "1") (pinfunction "PD3(INT1)_1") (pintype "bidirectional"))
    )
    (net (code "10") (name "/CS_SD") (class "Default")
      (node (ref "U$1") (pin "CS2") (pinfunction "CS_CS2") (pintype "input"))
      (node (ref "U1") (pin "14") (pinfunction "PB2(SS/OC1B)_14") (pintype "bidirectional"))
    )
    (net (code "11") (name "/CS_SHIFT_REG") (class "Default")
      (node (ref "R3") (pin "2") (pinfunction "2_2") (pintype "passive"))
      (node (ref "SHIFT_0") (pin "12") (pinfunction "RCLK_12") (pintype "input"))
      (node (ref "SHIFT_1") (pin "12") (pinfunction "RCLK_12") (pintype "input"))
      (node (ref "U1") (pin "25") (pinfunction "PC2(ADC2)_25") (pintype "bidirectional"))
    )
    (net (code "12") (name "/DTR") (class "Default")
      (node (ref "C5") (pin "1") (pinfunction "1_1") (pintype "passive"))
      (node (ref "JP1") (pin "6") (pinfunction "6_6") (pintype "passive"))
    )
    (net (code "13") (name "/GATE") (class "Default")
      (node (ref "BJT") (pin "3") (pinfunction "C_3") (pintype "passive"))
      (node (ref "P-FET") (pin "1") (pinfunction "G_1") (pintype "passive"))
      (node (ref "R33") (pin "1") (pinfunction "1_1") (pintype "passive"))
    )
    (net (code "14") (name "/HALL0_GND") (class "Default")
      (node (ref "A139_HALL0") (pin "P$3_4") (pinfunction "P$3_P$3_4") (pintype "bidirectional"))
      (node (ref "C50") (pin "2") (pinfunction "2_2") (pintype "passive"))
      (node (ref "HALL0_HEADER") (pin "P$1") (pinfunction "1_P$1") (pintype "passive"))
    )
    (net (code "15") (name "/HALL0_OUTPUT") (class "Default")
      (node (ref "HALL0") (pin "4") (pinfunction "4_4") (pintype "passive"))
      (node (ref "U$2") (pin "9") (pinfunction "X0_9") (pintype "input"))
    )
    (net (code "16") (name "/HALL0_VCC") (class "Default")
      (node (ref "A139_HALL0") (pin "P$1") (pinfunction "P$1_P$1") (pintype "bidirectional"))
      (node (ref "A139_HALL0") (pin "P$6") (pinfunction "P$6_P$6") (pintype "bidirectional"))
      (node (ref "C50") (pin "1") (pinfunction "1_1") (pintype "passive"))
      (node (ref "HALL0_HEADER") (pin "P$2") (pinfunction "2_P$2") (pintype "passive"))
    )
    (net (code "17") (name "/HALL0_VOUT") (class "Default")
      (node (ref "A139_HALL0") (pin "P$2") (pinfunction "P$2_P$2") (pintype "bidirectional"))
      (node (ref "HALL0_HEADER") (pin "P$3") (pinfunction "3_P$3") (pintype "passive"))
    )
    (net (code "18") (name "/HALL0_~{SLEEP_IN}") (class "Default")
      (node (ref "HALL0_HEADER") (pin "P$4") (pinfunction "4_P$4") (pintype "passive"))
      (node (ref "R50") (pin "1") (pinfunction "1_1") (pintype "passive"))
    )
    (net (code "19") (name "/HALL0_~{SLEEP}") (class "Default")
      (node (ref "HALL0") (pin "3") (pinfunction "3_3") (pintype "passive"))
      (node (ref "SHIFT_0") (pin "15") (pinfunction "QA_15") (pintype "tri_state"))
    )
    (net (code "20") (name "/HALL1_GND") (class "Default")
      (node (ref "A139_HALL1") (pin "P$3_4") (pinfunction "P$3_P$3_4") (pintype "bidirectional"))
      (node (ref "C51") (pin "2") (pinfunction "2_2") (pintype "passive"))
      (node (ref "HALL1_HEADER") (pin "P$1") (pinfunction "1_P$1") (pintype "passive"))
    )
    (net (code "21") (name "/HALL1_OUTPUT") (class "Default")
      (node (ref "HALL1") (pin "4") (pinfunction "4_4") (pintype "passive"))
      (node (ref "U$2") (pin "8") (pinfunction "X1_8") (pintype "input"))
    )
    (net (code "22") (name "/HALL1_VCC") (class "Default")
      (node (ref "A139_HALL1") (pin "P$1") (pinfunction "P$1_P$1") (pintype "bidirectional"))
      (node (ref "A139_HALL1") (pin "P$6") (pinfunction "P$6_P$6") (pintype "bidirectional"))
      (node (ref "C51") (pin "1") (pinfunction "1_1") (pintype "passive"))
      (node (ref "HALL1_HEADER") (pin "P$2") (pinfunction "2_P$2") (pintype "passive"))
    )
    (net (code "23") (name "/HALL1_VOUT") (class "Default")
      (node (ref "A139_HALL1") (pin "P$2") (pinfunction "P$2_P$2") (pintype "bidirectional"))
      (node (ref "HALL1_HEADER") (pin "P$3") (pinfunction "3_P$3") (pintype "passive"))
    )
    (net (code "24") (name "/HALL1_~{SLEEP_IN}") (class "Default")
      (node (ref "HALL1_HEADER") (pin "P$4") (pinfunction "4_P$4") (pintype "passive"))
      (node (ref "R51") (pin "1") (pinfunction "1_1") (pintype "passive"))
    )
    (net (code "25") (name "/HALL1_~{SLEEP}") (class "Default")
      (node (ref "HALL1") (pin "3") (pinfunction "3_3") (pintype "passive"))
      (node (ref "SHIFT_0") (pin "1") (pinfunction "QB_1") (pintype "tri_state"))
    )
    (net (code "26") (name "/HALL2_GND") (class "Default")
      (node (ref "A139_HALL2") (pin "P$3_4") (pinfunction "P$3_P$3_4") (pintype "bidirectional"))
      (node (ref "C52") (pin "2") (pinfunction "2_2") (pintype "passive"))
      (node (ref "HALL2_HEADER") (pin "P$1") (pinfunction "1_P$1") (pintype "passive"))
    )
    (net (code "27") (name "/HALL2_OUTPUT") (class "Default")
      (node (ref "HALL2") (pin "4") (pinfunction "4_4") (pintype "passive"))
      (node (ref "U$2") (pin "7") (pinfunction "X2_7") (pintype "input"))
    )
    (net (code "28") (name "/HALL2_VCC") (class "Default")
      (node (ref "A139_HALL2") (pin "P$1") (pinfunction "P$1_P$1") (pintype "bidirectional"))
      (node (ref "A139_HALL2") (pin "P$6") (pinfunction "P$6_P$6") (pintype "bidirectional"))
      (node (ref "C52") (pin "1") (pinfunction "1_1") (pintype "passive"))
      (node (ref "HALL2_HEADER") (pin "P$2") (pinfunction "2_P$2") (pintype "passive"))
    )
    (net (code "29") (name "/HALL2_VOUT") (class "Default")
      (node (ref "A139_HALL2") (pin "P$2") (pinfunction "P$2_P$2") (pintype "bidirectional"))
      (node (ref "HALL2_HEADER") (pin "P$3") (pinfunction "3_P$3") (pintype "passive"))
    )
    (net (code "30") (name "/HALL2_~{SLEEP_IN}") (class "Default")
      (node (ref "HALL2_HEADER") (pin "P$4") (pinfunction "4_P$4") (pintype "passive"))
      (node (ref "R52") (pin "1") (pinfunction "1_1") (pintype "passive"))
    )
    (net (code "31") (name "/HALL2_~{SLEEP}") (class "Default")
      (node (ref "HALL2") (pin "3") (pinfunction "3_3") (pintype "passive"))
      (node (ref "SHIFT_0") (pin "2") (pinfunction "QC_2") (pintype "tri_state"))
    )
    (net (code "32") (name "/HALL3_GND") (class "Default")
      (node (ref "A139_HALL3") (pin "P$3_4") (pinfunction "P$3_P$3_4") (pintype "bidirectional"))
      (node (ref "C53") (pin "2") (pinfunction "2_2") (pintype "passive"))
      (node (ref "HALL3_HEADER") (pin "P$1") (pinfunction "1_P$1") (pintype "passive"))
    )
    (net (code "33") (name "/HALL3_OUTPUT") (class "Default")
      (node (ref "HALL3") (pin "4") (pinfunction "4_4") (pintype "passive"))
      (node (ref "U$2") (pin "6") (pinfunction "X3_6") (pintype "input"))
    )
    (net (code "34") (name "/HALL3_VCC") (class "Default")
      (node (ref "A139_HALL3") (pin "P$1") (pinfunction "P$1_P$1") (pintype "bidirectional"))
      (node (ref "A139_HALL3") (pin "P$6") (pinfunction "P$6_P$6") (pintype "bidirectional"))
      (node (ref "C53") (pin "1") (pinfunction "1_1") (pintype "passive"))
      (node (ref "HALL3_HEADER") (pin "P$2") (pinfunction "2_P$2") (pintype "passive"))
    )
    (net (code "35") (name "/HALL3_VOUT") (class "Default")
      (node (ref "A139_HALL3") (pin "P$2") (pinfunction "P$2_P$2") (pintype "bidirectional"))
      (node (ref "HALL3_HEADER") (pin "P$3") (pinfunction "3_P$3") (pintype "passive"))
    )
    (net (code "36") (name "/HALL3_~{SLEEP_IN}") (class "Default")
      (node (ref "HALL3_HEADER") (pin "P$4") (pinfunction "4_P$4") (pintype "passive"))
      (node (ref "R53") (pin "1") (pinfunction "1_1") (pintype "passive"))
    )
    (net (code "37") (name "/HALL3_~{SLEEP}") (class "Default")
      (node (ref "HALL3") (pin "3") (pinfunction "3_3") (pintype "passive"))
      (node (ref "SHIFT_0") (pin "3") (pinfunction "QD_3") (pintype "tri_state"))
    )
    (net (code "38") (name "/HALL4_GND") (class "Default")
      (node (ref "A139_HALL4") (pin "P$3_4") (pinfunction "P$3_P$3_4") (pintype "bidirectional"))
      (node (ref "C54") (pin "2") (pinfunction "2_2") (pintype "passive"))
      (node (ref "HALL4_HEADER") (pin "P$1") (pinfunction "1_P$1") (pintype "passive"))
    )
    (net (code "39") (name "/HALL4_OUTPUT") (class "Default")
      (node (ref "HALL4") (pin "4") (pinfunction "4_4") (pintype "passive"))
      (node (ref "U$2") (pin "5") (pinfunction "X4_5") (pintype "input"))
    )
    (net (code "40") (name "/HALL4_VCC") (class "Default")
      (node (ref "A139_HALL4") (pin "P$1") (pinfunction "P$1_P$1") (pintype "bidirectional"))
      (node (ref "A139_HALL4") (pin "P$6") (pinfunction "P$6_P$6") (pintype "bidirectional"))
      (node (ref "C54") (pin "1") (pinfunction "1_1") (pintype "passive"))
      (node (ref "HALL4_HEADER") (pin "P$2") (pinfunction "2_P$2") (pintype "passive"))
    )
    (net (code "41") (name "/HALL4_VOUT") (class "Default")
      (node (ref "A139_HALL4") (pin "P$2") (pinfunction "P$2_P$2") (pintype "bidirectional"))
      (node (ref "HALL4_HEADER") (pin "P$3") (pinfunction "3_P$3") (pintype "passive"))
    )
    (net (code "42") (name "/HALL4_~{SLEEP_IN}") (class "Default")
      (node (ref "HALL4_HEADER") (pin "P$4") (pinfunction "4_P$4") (pintype "passive"))
      (node (ref "R54") (pin "1") (pinfunction "1_1") (pintype "passive"))
    )
    (net (code "43") (name "/HALL4_~{SLEEP}") (class "Default")
      (node (ref "HALL4") (pin "3") (pinfunction "3_3") (pintype "passive"))
      (node (ref "SHIFT_0") (pin "4") (pinfunction "QE_4") (pintype "tri_state"))
    )
    (net (code "44") (name "/HALL5_GND") (class "Default")
      (node (ref "A139_HALL5") (pin "P$3_4") (pinfunction "P$3_P$3_4") (pintype "bidirectional"))
      (node (ref "C55") (pin "2") (pinfunction "2_2") (pintype "passive"))
      (node (ref "HALL5_HEADER") (pin "P$1") (pinfunction "1_P$1") (pintype "passive"))
    )
    (net (code "45") (name "/HALL5_OUTPUT") (class "Default")
      (node (ref "HALL5") (pin "4") (pinfunction "4_4") (pintype "passive"))
      (node (ref "U$2") (pin "4") (pinfunction "X5_4") (pintype "input"))
    )
    (net (code "46") (name "/HALL5_VCC") (class "Default")
      (node (ref "A139_HALL5") (pin "P$1") (pinfunction "P$1_P$1") (pintype "bidirectional"))
      (node (ref "A139_HALL5") (pin "P$6") (pinfunction "P$6_P$6") (pintype "bidirectional"))
      (node (ref "C55") (pin "1") (pinfunction "1_1") (pintype "passive"))
      (node (ref "HALL5_HEADER") (pin "P$2") (pinfunction "2_P$2") (pintype "passive"))
    )
    (net (code "47") (name "/HALL5_VOUT") (class "Default")
      (node (ref "A139_HALL5") (pin "P$2") (pinfunction "P$2_P$2") (pintype "bidirectional"))
      (node (ref "HALL5_HEADER") (pin "P$3") (pinfunction "3_P$3") (pintype "passive"))
    )
    (net (code "48") (name "/HALL5_~{SLEEP_IN}") (class "Default")
      (node (ref "HALL5_HEADER") (pin "P$4") (pinfunction "4_P$4") (pintype "passive"))
      (node (ref "R55") (pin "1") (pinfunction "1_1") (pintype "passive"))
    )
    (net (code "49") (name "/HALL5_~{SLEEP}") (class "Default")
      (node (ref "HALL5") (pin "3") (pinfunction "3_3") (pintype "passive"))
      (node (ref "SHIFT_0") (pin "5") (pinfunction "QF_5") (pintype "tri_state"))
    )
    (net (code "50") (name "/HALL6_GND") (class "Default")
      (node (ref "A139_HALL6") (pin "P$3_4") (pinfunction "P$3_P$3_4") (pintype "bidirectional"))
      (node (ref "C56") (pin "2") (pinfunction "2_2") (pintype "passive"))
      (node (ref "HALL6_HEADER") (pin "P$1") (pinfunction "1_P$1") (pintype "passive"))
    )
    (net (code "51") (name "/HALL6_OUTPUT") (class "Default")
      (node (ref "HALL6") (pin "4") (pinfunction "4_4") (pintype "passive"))
      (node (ref "U$2") (pin "3") (pinfunction "X6_3") (pintype "input"))
    )
    (net (code "52") (name "/HALL6_VCC") (class "Default")
      (node (ref "A139_HALL6") (pin "P$1") (pinfunction "P$1_P$1") (pintype "bidirectional"))
      (node (ref "A139_HALL6") (pin "P$6") (pinfunction "P$6_P$6") (pintype "bidirectional"))
      (node (ref "C56") (pin "1") (pinfunction "1_1") (pintype "passive"))
      (node (ref "HALL6_HEADER") (pin "P$2") (pinfunction "2_P$2") (pintype "passive"))
    )
    (net (code "53") (name "/HALL6_VOUT") (class "Default")
      (node (ref "A139_HALL6") (pin "P$2") (pinfunction "P$2_P$2") (pintype "bidirectional"))
      (node (ref "HALL6_HEADER") (pin "P$3") (pinfunction "3_P$3") (pintype "passive"))
    )
    (net (code "54") (name "/HALL6_~{SLEEP_IN}") (class "Default")
      (node (ref "HALL6_HEADER") (pin "P$4") (pinfunction "4_P$4") (pintype "passive"))
      (node (ref "R56") (pin "1") (pinfunction "1_1") (pintype "passive"))
    )
    (net (code "55") (name "/HALL6_~{SLEEP}") (class "Default")
      (node (ref "HALL6") (pin "3") (pinfunction "3_3") (pintype "passive"))
      (node (ref "SHIFT_0") (pin "6") (pinfunction "QG_6") (pintype "tri_state"))
    )
    (net (code "56") (name "/HALL7_GND") (class "Default")
      (node (ref "A139_HALL7") (pin "P$3_4") (pinfunction "P$3_P$3_4") (pintype "bidirectional"))
      (node (ref "C57") (pin "2") (pinfunction "2_2") (pintype "passive"))
      (node (ref "HALL7_HEADER") (pin "P$1") (pinfunction "1_P$1") (pintype "passive"))
    )
    (net (code "57") (name "/HALL7_OUTPUT") (class "Default")
      (node (ref "HALL7") (pin "4") (pinfunction "4_4") (pintype "passive"))
      (node (ref "U$2") (pin "2") (pinfunction "X7_2") (pintype "input"))
    )
    (net (code "58") (name "/HALL7_VCC") (class "Default")
      (node (ref "A139_HALL7") (pin "P$1") (pinfunction "P$1_P$1") (pintype "bidirectional"))
      (node (ref "A139_HALL7") (pin "P$6") (pinfunction "P$6_P$6") (pintype "bidirectional"))
      (node (ref "C57") (pin "1") (pinfunction "1_1") (pintype "passive"))
      (node (ref "HALL7_HEADER") (pin "P$2") (pinfunction "2_P$2") (pintype "passive"))
    )
    (net (code "59") (name "/HALL7_VOUT") (class "Default")
      (node (ref "A139_HALL7") (pin "P$2") (pinfunction "P$2_P$2") (pintype "bidirectional"))
      (node (ref "HALL7_HEADER") (pin "P$3") (pinfunction "3_P$3") (pintype "passive"))
    )
    (net (code "60") (name "/HALL7_~{SLEEP_IN}") (class "Default")
      (node (ref "HALL7_HEADER") (pin "P$4") (pinfunction "4_P$4") (pintype "passive"))
      (node (ref "R57") (pin "1") (pinfunction "1_1") (pintype "passive"))
    )
    (net (code "61") (name "/HALL7_~{SLEEP}") (class "Default")
      (node (ref "HALL7") (pin "3") (pinfunction "3_3") (pintype "passive"))
      (node (ref "SHIFT_0") (pin "7") (pinfunction "QH_7") (pintype "tri_state"))
    )
    (net (code "62") (name "/HALL8_GND") (class "Default")
      (node (ref "A139_HALL8") (pin "P$3_4") (pinfunction "P$3_P$3_4") (pintype "bidirectional"))
      (node (ref "C58") (pin "2") (pinfunction "2_2") (pintype "passive"))
      (node (ref "HALL8_HEADER") (pin "P$1") (pinfunction "1_P$1") (pintype "passive"))
    )
    (net (code "63") (name "/HALL8_OUTPUT") (class "Default")
      (node (ref "HALL8") (pin "4") (pinfunction "4_4") (pintype "passive"))
      (node (ref "U$2") (pin "23") (pinfunction "X8_23") (pintype "input"))
    )
    (net (code "64") (name "/HALL8_VCC") (class "Default")
      (node (ref "A139_HALL8") (pin "P$1") (pinfunction "P$1_P$1") (pintype "bidirectional"))
      (node (ref "A139_HALL8") (pin "P$6") (pinfunction "P$6_P$6") (pintype "bidirectional"))
      (node (ref "C58") (pin "1") (pinfunction "1_1") (pintype "passive"))
      (node (ref "HALL8_HEADER") (pin "P$2") (pinfunction "2_P$2") (pintype "passive"))
    )
    (net (code "65") (name "/HALL8_VOUT") (class "Default")
      (node (ref "A139_HALL8") (pin "P$2") (pinfunction "P$2_P$2") (pintype "bidirectional"))
      (node (ref "HALL8_HEADER") (pin "P$3") (pinfunction "3_P$3") (pintype "passive"))
    )
    (net (code "66") (name "/HALL8_~{SLEEP_IN}") (class "Default")
      (node (ref "HALL8_HEADER") (pin "P$4") (pinfunction "4_P$4") (pintype "passive"))
      (node (ref "R58") (pin "1") (pinfunction "1_1") (pintype "passive"))
    )
    (net (code "67") (name "/HALL8_~{SLEEP}") (class "Default")
      (node (ref "HALL8") (pin "3") (pinfunction "3_3") (pintype "passive"))
      (node (ref "SHIFT_1") (pin "15") (pinfunction "QA_15") (pintype "tri_state"))
    )
    (net (code "68") (name "/HALL9_GND") (class "Default")
      (node (ref "A139_HALL9") (pin "P$3_4") (pinfunction "P$3_P$3_4") (pintype "bidirectional"))
      (node (ref "C59") (pin "2") (pinfunction "2_2") (pintype "passive"))
      (node (ref "HALL9_HEADER") (pin "P$1") (pinfunction "1_P$1") (pintype "passive"))
    )
    (net (code "69") (name "/HALL9_OUTPUT") (class "Default")
      (node (ref "HALL9") (pin "4") (pinfunction "4_4") (pintype "passive"))
      (node (ref "U$2") (pin "22") (pinfunction "X9_22") (pintype "input"))
    )
    (net (code "70") (name "/HALL9_VCC") (class "Default")
      (node (ref "A139_HALL9") (pin "P$1") (pinfunction "P$1_P$1") (pintype "bidirectional"))
      (node (ref "A139_HALL9") (pin "P$6") (pinfunction "P$6_P$6") (pintype "bidirectional"))
      (node (ref "C59") (pin "1") (pinfunction "1_1") (pintype "passive"))
      (node (ref "HALL9_HEADER") (pin "P$2") (pinfunction "2_P$2") (pintype "passive"))
    )
    (net (code "71") (name "/HALL9_VOUT") (class "Default")
      (node (ref "A139_HALL9") (pin "P$2") (pinfunction "P$2_P$2") (pintype "bidirectional"))
      (node (ref "HALL9_HEADER") (pin "P$3") (pinfunction "3_P$3") (pintype "passive"))
    )
    (net (code "72") (name "/HALL9_~{SLEEP_IN}") (class "Default")
      (node (ref "HALL9_HEADER") (pin "P$4") (pinfunction "4_P$4") (pintype "passive"))
      (node (ref "R59") (pin "1") (pinfunction "1_1") (pintype "passive"))
    )
    (net (code "73") (name "/HALL9_~{SLEEP}") (class "Default")
      (node (ref "HALL9") (pin "3") (pinfunction "3_3") (pintype "passive"))
      (node (ref "SHIFT_1") (pin "1") (pinfunction "QB_1") (pintype "tri_state"))
    )
    (net (code "74") (name "/HALL10_GND") (class "Default")
      (node (ref "A139_HALL10") (pin "P$3_4") (pinfunction "P$3_P$3_4") (pintype "bidirectional"))
      (node (ref "C60") (pin "2") (pinfunction "2_2") (pintype "passive"))
      (node (ref "HALL10_HEADER") (pin "P$1") (pinfunction "1_P$1") (pintype "passive"))
    )
    (net (code "75") (name "/HALL10_OUTPUT") (class "Default")
      (node (ref "HALL10") (pin "4") (pinfunction "4_4") (pintype "passive"))
      (node (ref "U$2") (pin "21") (pinfunction "X10_21") (pintype "input"))
    )
    (net (code "76") (name "/HALL10_VCC") (class "Default")
      (node (ref "A139_HALL10") (pin "P$1") (pinfunction "P$1_P$1") (pintype "bidirectional"))
      (node (ref "A139_HALL10") (pin "P$6") (pinfunction "P$6_P$6") (pintype "bidirectional"))
      (node (ref "C60") (pin "1") (pinfunction "1_1") (pintype "passive"))
      (node (ref "HALL10_HEADER") (pin "P$2") (pinfunction "2_P$2") (pintype "passive"))
    )
    (net (code "77") (name "/HALL10_VOUT") (class "Default")
      (node (ref "A139_HALL10") (pin "P$2") (pinfunction "P$2_P$2") (pintype "bidirectional"))
      (node (ref "HALL10_HEADER") (pin "P$3") (pinfunction "3_P$3") (pintype "passive"))
    )
    (net (code "78") (name "/HALL10_~{SLEEP_IN}") (class "Default")
      (node (ref "HALL10_HEADER") (pin "P$4") (pinfunction "4_P$4") (pintype "passive"))
      (node (ref "R60") (pin "1") (pinfunction "1_1") (pintype "passive"))
    )
    (net (code "79") (name "/HALL10_~{SLEEP}") (class "Default")
      (node (ref "HALL10") (pin "3") (pinfunction "3_3") (pintype "passive"))
      (node (ref "SHIFT_1") (pin "2") (pinfunction "QC_2") (pintype "tri_state"))
    )
    (net (code "80") (name "/HALL11_GND") (class "Default")
      (node (ref "A139_HALL11") (pin "P$3_4") (pinfunction "P$3_P$3_4") (pintype "bidirectional"))
      (node (ref "C61") (pin "2") (pinfunction "2_2") (pintype "passive"))
      (node (ref "HALL11_HEADER") (pin "P$1") (pinfunction "1_P$1") (pintype "passive"))
    )
    (net (code "81") (name "/HALL11_OUTPUT") (class "Default")
      (node (ref "HALL11") (pin "4") (pinfunction "4_4") (pintype "passive"))
      (node (ref "U$2") (pin "20") (pinfunction "X11_20") (pintype "input"))
    )
    (net (code "82") (name "/HALL11_VCC") (class "Default")
      (node (ref "A139_HALL11") (pin "P$1") (pinfunction "P$1_P$1") (pintype "bidirectional"))
      (node (ref "A139_HALL11") (pin "P$6") (pinfunction "P$6_P$6") (pintype "bidirectional"))
      (node (ref "C61") (pin "1") (pinfunction "1_1") (pintype "passive"))
      (node (ref "HALL11_HEADER") (pin "P$2") (pinfunction "2_P$2") (pintype "passive"))
    )
    (net (code "83") (name "/HALL11_VOUT") (class "Default")
      (node (ref "A139_HALL11") (pin "P$2") (pinfunction "P$2_P$2") (pintype "bidirectional"))
      (node (ref "HALL11_HEADER") (pin "P$3") (pinfunction "3_P$3") (pintype "passive"))
    )
    (net (code "84") (name "/HALL11_~{SLEEP_IN}") (class "Default")
      (node (ref "HALL11_HEADER") (pin "P$4") (pinfunction "4_P$4") (pintype "passive"))
      (node (ref "R61") (pin "1") (pinfunction "1_1") (pintype "passive"))
    )
    (net (code "85") (name "/HALL11_~{SLEEP}") (class "Default")
      (node (ref "HALL11") (pin "3") (pinfunction "3_3") (pintype "passive"))
      (node (ref "SHIFT_1") (pin "3") (pinfunction "QD_3") (pintype "tri_state"))
    )
    (net (code "86") (name "/HALL12_GND") (class "Default")
      (node (ref "A139_HALL12") (pin "P$3_4") (pinfunction "P$3_P$3_4") (pintype "bidirectional"))
      (node (ref "C62") (pin "2") (pinfunction "2_2") (pintype "passive"))
      (node (ref "HALL12_HEADER") (pin "P$1") (pinfunction "1_P$1") (pintype "passive"))
    )
    (net (code "87") (name "/HALL12_OUTPUT") (class "Default")
      (node (ref "HALL12") (pin "4") (pinfunction "4_4") (pintype "passive"))
      (node (ref "U$2") (pin "19") (pinfunction "X12_19") (pintype "input"))
    )
    (net (code "88") (name "/HALL12_VCC") (class "Default")
      (node (ref "A139_HALL12") (pin "P$1") (pinfunction "P$1_P$1") (pintype "bidirectional"))
      (node (ref "A139_HALL12") (pin "P$6") (pinfunction "P$6_P$6") (pintype "bidirectional"))
      (node (ref "C62") (pin "1") (pinfunction "1_1") (pintype "passive"))
      (node (ref "HALL12_HEADER") (pin "P$2") (pinfunction "2_P$2") (pintype "passive"))
    )
    (net (code "89") (name "/HALL12_VOUT") (class "Default")
      (node (ref "A139_HALL12") (pin "P$2") (pinfunction "P$2_P$2") (pintype "bidirectional"))
      (node (ref "HALL12_HEADER") (pin "P$3") (pinfunction "3_P$3") (pintype "passive"))
    )
    (net (code "90") (name "/HALL12_~{SLEEP_IN}") (class "Default")
      (node (ref "HALL12_HEADER") (pin "P$4") (pinfunction "4_P$4") (pintype "passive"))
      (node (ref "R62") (pin "1") (pinfunction "1_1") (pintype "passive"))
    )
    (net (code "91") (name "/HALL12_~{SLEEP}") (class "Default")
      (node (ref "HALL12") (pin "3") (pinfunction "3_3") (pintype "passive"))
      (node (ref "SHIFT_1") (pin "4") (pinfunction "QE_4") (pintype "tri_state"))
    )
    (net (code "92") (name "/HALL13_GND") (class "Default")
      (node (ref "A139_HALL13") (pin "P$3_4") (pinfunction "P$3_P$3_4") (pintype "bidirectional"))
      (node (ref "C63") (pin "2") (pinfunction "2_2") (pintype "passive"))
      (node (ref "HALL13_HEADER") (pin "P$1") (pinfunction "1_P$1") (pintype "passive"))
    )
    (net (code "93") (name "/HALL13_OUTPUT") (class "Default")
      (node (ref "HALL13") (pin "4") (pinfunction "4_4") (pintype "passive"))
      (node (ref "U$2") (pin "18") (pinfunction "X13_18") (pintype "input"))
    )
    (net (code "94") (name "/HALL13_VCC") (class "Default")
      (node (ref "A139_HALL13") (pin "P$1") (pinfunction "P$1_P$1") (pintype "bidirectional"))
      (node (ref "A139_HALL13") (pin "P$6") (pinfunction "P$6_P$6") (pintype "bidirectional"))
      (node (ref "C63") (pin "1") (pinfunction "1_1") (pintype "passive"))
      (node (ref "HALL13_HEADER") (pin "P$2") (pinfunction "2_P$2") (pintype "passive"))
    )
    (net (code "95") (name "/HALL13_VOUT") (class "Default")
      (node (ref "A139_HALL13") (pin "P$2") (pinfunction "P$2_P$2") (pintype "bidirectional"))
      (node (ref "HALL13_HEADER") (pin "P$3") (pinfunction "3_P$3") (pintype "passive"))
    )
    (net (code "96") (name "/HALL13_~{SLEEP_IN}") (class "Default")
      (node (ref "HALL13_HEADER") (pin "P$4") (pinfunction "4_P$4") (pintype "passive"))
      (node (ref "R63") (pin "1") (pinfunction "1_1") (pintype "passive"))
    )
    (net (code "97") (name "/HALL13_~{SLEEP}") (class "Default")
      (node (ref "HALL13") (pin "3") (pinfunction "3_3") (pintype "passive"))
      (node (ref "SHIFT_1") (pin "5") (pinfunction "QF_5") (pintype "tri_state"))
    )
    (net (code "98") (name "/HALL14_GND") (class "Default")
      (node (ref "A139_HALL14") (pin "P$3_4") (pinfunction "P$3_P$3_4") (pintype "bidirectional"))
      (node (ref "C64") (pin "2") (pinfunction "2_2") (pintype "passive"))
      (node (ref "HALL14_HEADER") (pin "P$1") (pinfunction "1_P$1") (pintype "passive"))
    )
    (net (code "99") (name "/HALL14_OUTPUT") (class "Default")
      (node (ref "HALL14") (pin "4") (pinfunction "4_4") (pintype "passive"))
      (node (ref "U$2") (pin "17") (pinfunction "X14_17") (pintype "input"))
    )
    (net (code "100") (name "/HALL14_VCC") (class "Default")
      (node (ref "A139_HALL14") (pin "P$1") (pinfunction "P$1_P$1") (pintype "bidirectional"))
      (node (ref "A139_HALL14") (pin "P$6") (pinfunction "P$6_P$6") (pintype "bidirectional"))
      (node (ref "C64") (pin "1") (pinfunction "1_1") (pintype "passive"))
      (node (ref "HALL14_HEADER") (pin "P$2") (pinfunction "2_P$2") (pintype "passive"))
    )
    (net (code "101") (name "/HALL14_VOUT") (class "Default")
      (node (ref "A139_HALL14") (pin "P$2") (pinfunction "P$2_P$2") (pintype "bidirectional"))
      (node (ref "HALL14_HEADER") (pin "P$3") (pinfunction "3_P$3") (pintype "passive"))
    )
    (net (code "102") (name "/HALL14_~{SLEEP_IN}") (class "Default")
      (node (ref "HALL14_HEADER") (pin "P$4") (pinfunction "4_P$4") (pintype "passive"))
      (node (ref "R64") (pin "1") (pinfunction "1_1") (pintype "passive"))
    )
    (net (code "103") (name "/HALL14_~{SLEEP}") (class "Default")
      (node (ref "HALL14") (pin "3") (pinfunction "3_3") (pintype "passive"))
      (node (ref "SHIFT_1") (pin "6") (pinfunction "QG_6") (pintype "tri_state"))
    )
    (net (code "104") (name "/HALL15_GND") (class "Default")
      (node (ref "A139_HALL15") (pin "P$3_4") (pinfunction "P$3_P$3_4") (pintype "bidirectional"))
      (node (ref "C65") (pin "2") (pinfunction "2_2") (pintype "passive"))
      (node (ref "HALL15_HEADER") (pin "P$1") (pinfunction "1_P$1") (pintype "passive"))
    )
    (net (code "105") (name "/HALL15_OUTPUT") (class "Default")
      (node (ref "HALL15") (pin "4") (pinfunction "4_4") (pintype "passive"))
      (node (ref "U$2") (pin "16") (pinfunction "X15_16") (pintype "input"))
    )
    (net (code "106") (name "/HALL15_VCC") (class "Default")
      (node (ref "A139_HALL15") (pin "P$1") (pinfunction "P$1_P$1") (pintype "bidirectional"))
      (node (ref "A139_HALL15") (pin "P$6") (pinfunction "P$6_P$6") (pintype "bidirectional"))
      (node (ref "C65") (pin "1") (pinfunction "1_1") (pintype "passive"))
      (node (ref "HALL15_HEADER") (pin "P$2") (pinfunction "2_P$2") (pintype "passive"))
    )
    (net (code "107") (name "/HALL15_VOUT") (class "Default")
      (node (ref "A139_HALL15") (pin "P$2") (pinfunction "P$2_P$2") (pintype "bidirectional"))
      (node (ref "HALL15_HEADER") (pin "P$3") (pinfunction "3_P$3") (pintype "passive"))
    )
    (net (code "108") (name "/HALL15_~{SLEEP_IN}") (class "Default")
      (node (ref "HALL15_HEADER") (pin "P$4") (pinfunction "4_P$4") (pintype "passive"))
      (node (ref "R65") (pin "1") (pinfunction "1_1") (pintype "passive"))
    )
    (net (code "109") (name "/HALL15_~{SLEEP}") (class "Default")
      (node (ref "HALL15") (pin "3") (pinfunction "3_3") (pintype "passive"))
      (node (ref "SHIFT_1") (pin "7") (pinfunction "QH_7") (pintype "tri_state"))
    )
    (net (code "110") (name "/HALL16_GND") (class "Default")
      (node (ref "A139_HALL16") (pin "P$3_4") (pinfunction "P$3_P$3_4") (pintype "bidirectional"))
      (node (ref "C66") (pin "2") (pinfunction "2_2") (pintype "passive"))
      (node (ref "HALL16_HEADER") (pin "P$1") (pinfunction "1_P$1") (pintype "passive"))
    )
    (net (code "111") (name "/HALL16_VCC") (class "Default")
      (node (ref "A139_HALL16") (pin "P$1") (pinfunction "P$1_P$1") (pintype "bidirectional"))
      (node (ref "A139_HALL16") (pin "P$6") (pinfunction "P$6_P$6") (pintype "bidirectional"))
      (node (ref "C66") (pin "1") (pinfunction "1_1") (pintype "passive"))
      (node (ref "HALL16_HEADER") (pin "P$2") (pinfunction "2_P$2") (pintype "passive"))
    )
    (net (code "112") (name "/HALL16_VOUT") (class "Default")
      (node (ref "A139_HALL16") (pin "P$2") (pinfunction "P$2_P$2") (pintype "bidirectional"))
      (node (ref "HALL16_HEADER") (pin "P$3") (pinfunction "3_P$3") (pintype "passive"))
    )
    (net (code "113") (name "/HALL16_~{SLEEP_IN}") (class "Default")
      (node (ref "HALL16_HEADER") (pin "P$4") (pinfunction "4_P$4") (pintype "passive"))
      (node (ref "R66") (pin "1") (pinfunction "1_1") (pintype "passive"))
    )
    (net (code "114") (name "/HALL17_GND") (class "Default")
      (node (ref "A139_HALL17") (pin "P$3_4") (pinfunction "P$3_P$3_4") (pintype "bidirectional"))
      (node (ref "C67") (pin "2") (pinfunction "2_2") (pintype "passive"))
      (node (ref "HALL17_HEADER") (pin "P$1") (pinfunction "1_P$1") (pintype "passive"))
    )
    (net (code "115") (name "/HALL17_VCC") (class "Default")
      (node (ref "A139_HALL17") (pin "P$1") (pinfunction "P$1_P$1") (pintype "bidirectional"))
      (node (ref "A139_HALL17") (pin "P$6") (pinfunction "P$6_P$6") (pintype "bidirectional"))
      (node (ref "C67") (pin "1") (pinfunction "1_1") (pintype "passive"))
      (node (ref "HALL17_HEADER") (pin "P$2") (pinfunction "2_P$2") (pintype "passive"))
    )
    (net (code "116") (name "/HALL17_VOUT") (class "Default")
      (node (ref "A139_HALL17") (pin "P$2") (pinfunction "P$2_P$2") (pintype "bidirectional"))
      (node (ref "HALL17_HEADER") (pin "P$3") (pinfunction "3_P$3") (pintype "passive"))
    )
    (net (code "117") (name "/HALL17_~{SLEEP_IN}") (class "Default")
      (node (ref "HALL17_HEADER") (pin "P$4") (pinfunction "4_P$4") (pintype "passive"))
      (node (ref "R67") (pin "1") (pinfunction "1_1") (pintype "passive"))
    )
    (net (code "118") (name "/HALL18_GND") (class "Default")
      (node (ref "A139_HALL18") (pin "P$3_4") (pinfunction "P$3_P$3_4") (pintype "bidirectional"))
      (node (ref "C68") (pin "2") (pinfunction "2_2") (pintype "passive"))
      (node (ref "HALL18_HEADER") (pin "P$1") (pinfunction "1_P$1") (pintype "passive"))
    )
    (net (code "119") (name "/HALL18_VCC") (class "Default")
      (node (ref "A139_HALL18") (pin "P$1") (pinfunction "P$1_P$1") (pintype "bidirectional"))
      (node (ref "A139_HALL18") (pin "P$6") (pinfunction "P$6_P$6") (pintype "bidirectional"))
      (node (ref "C68") (pin "1") (pinfunction "1_1") (pintype "passive"))
      (node (ref "HALL18_HEADER") (pin "P$2") (pinfunction "2_P$2") (pintype "passive"))
    )
    (net (code "120") (name "/HALL18_VOUT") (class "Default")
      (node (ref "A139_HALL18") (pin "P$2") (pinfunction "P$2_P$2") (pintype "bidirectional"))
      (node (ref "HALL18_HEADER") (pin "P$3") (pinfunction "3_P$3") (pintype "passive"))
    )
    (net (code "121") (name "/HALL18_~{SLEEP_IN}") (class "Default")
      (node (ref "HALL18_HEADER") (pin "P$4") (pinfunction "4_P$4") (pintype "passive"))
      (node (ref "R68") (pin "1") (pinfunction "1_1") (pintype "passive"))
    )
    (net (code "122") (name "/HALL19_GND") (class "Default")
      (node (ref "A139_HALL19") (pin "P$3_4") (pinfunction "P$3_P$3_4") (pintype "bidirectional"))
      (node (ref "C69") (pin "2") (pinfunction "2_2") (pintype "passive"))
      (node (ref "HALL19_HEADER") (pin "P$1") (pinfunction "1_P$1") (pintype "passive"))
    )
    (net (code "123") (name "/HALL19_VCC") (class "Default")
      (node (ref "A139_HALL19") (pin "P$1") (pinfunction "P$1_P$1") (pintype "bidirectional"))
      (node (ref "A139_HALL19") (pin "P$6") (pinfunction "P$6_P$6") (pintype "bidirectional"))
      (node (ref "C69") (pin "1") (pinfunction "1_1") (pintype "passive"))
      (node (ref "HALL19_HEADER") (pin "P$2") (pinfunction "2_P$2") (pintype "passive"))
    )
    (net (code "124") (name "/HALL19_VOUT") (class "Default")
      (node (ref "A139_HALL19") (pin "P$2") (pinfunction "P$2_P$2") (pintype "bidirectional"))
      (node (ref "HALL19_HEADER") (pin "P$3") (pinfunction "3_P$3") (pintype "passive"))
    )
    (net (code "125") (name "/HALL19_~{SLEEP_IN}") (class "Default")
      (node (ref "HALL19_HEADER") (pin "P$4") (pinfunction "4_P$4") (pintype "passive"))
      (node (ref "R69") (pin "1") (pinfunction "1_1") (pintype "passive"))
    )
    (net (code "126") (name "/LED_GRN") (class "Default")
      (node (ref "R2") (pin "2") (pinfunction "2_2") (pintype "passive"))
      (node (ref "U1") (pin "26") (pinfunction "PC3(ADC3)_26") (pintype "bidirectional"))
    )
    (net (code "127") (name "/LED_RED") (class "Default")
      (node (ref "R1") (pin "2") (pinfunction "2_2") (pintype "passive"))
      (node (ref "U1") (pin "2") (pinfunction "PD4(XCK/T0)_2") (pintype "bidirectional"))
    )
    (net (code "128") (name "/MISO") (class "Default")
      (node (ref "J1") (pin "1") (pinfunction "1_1") (pintype "passive"))
      (node (ref "U$1") (pin "MISO7") (pinfunction "DATA_OUT_MISO_MISO7") (pintype "output"))
      (node (ref "U1") (pin "16") (pinfunction "PB4(MISO)_16") (pintype "bidirectional"))
    )
    (net (code "129") (name "/MOSI") (class "Default")
      (node (ref "J1") (pin "4") (pinfunction "4_4") (pintype "passive"))
      (node (ref "SHIFT_0") (pin "14") (pinfunction "SER_14") (pintype "input"))
      (node (ref "U$1") (pin "MOSI3") (pinfunction "DATA_IN_MOSI_MOSI3") (pintype "input"))
      (node (ref "U1") (pin "15") (pinfunction "PB3(MOSI/OC2)_15") (pintype "bidirectional"))
    )
    (net (code "130") (name "/MUX_S0") (class "Default")
      (node (ref "U$2") (pin "10") (pinfunction "S0_10") (pintype "input"))
      (node (ref "U1") (pin "13") (pinfunction "PB1(OC1A)_13") (pintype "bidirectional"))
    )
    (net (code "131") (name "/MUX_S1") (class "Default")
      (node (ref "U$2") (pin "11") (pinfunction "S1_11") (pintype "input"))
      (node (ref "U1") (pin "9") (pinfunction "PD5(T1)_9") (pintype "bidirectional"))
    )
    (net (code "132") (name "/MUX_S2") (class "Default")
      (node (ref "U$2") (pin "14") (pinfunction "S2_14") (pintype "input"))
      (node (ref "U1") (pin "10") (pinfunction "PD6(AIN0)_10") (pintype "bidirectional"))
    )
    (net (code "133") (name "/MUX_S3") (class "Default")
      (node (ref "U$2") (pin "13") (pinfunction "S3_13") (pintype "input"))
      (node (ref "U1") (pin "11") (pinfunction "PD7(AIN1)_11") (pintype "bidirectional"))
    )
    (net (code "134") (name "/MUX_~{EN}") (class "Default")
      (node (ref "R28") (pin "1") (pinfunction "1_1") (pintype "passive"))
      (node (ref "U$2") (pin "15") (pinfunction "~{E}_15") (pintype "input"))
      (node (ref "U1") (pin "12") (pinfunction "PB0(ICP)_12") (pintype "bidirectional"))
    )
    (net (code "135") (name "/PB7") (class "Default")
      (node (ref "PB7") (pin "1") (pinfunction "P$1_1") (pintype "bidirectional"))
      (node (ref "U1") (pin "8") (pinfunction "PB7(XTAL2/TOSC2)_8") (pintype "bidirectional"))
    )
    (net (code "136") (name "/RESET") (class "Default")
      (node (ref "C5") (pin "2") (pinfunction "2_2") (pintype "passive"))
      (node (ref "J1") (pin "5") (pinfunction "5_5") (pintype "passive"))
      (node (ref "R6") (pin "1") (pinfunction "1_1") (pintype "passive"))
      (node (ref "RESET") (pin "S$1") (pinfunction "S1_S$1") (pintype "passive"))
      (node (ref "U$3") (pin "1") (pinfunction "P$1_1") (pintype "bidirectional"))
      (node (ref "U1") (pin "29") (pinfunction "PC6(/RESET)_29") (pintype "bidirectional"))
    )
    (net (code "137") (name "/SCK") (class "Default")
      (node (ref "J1") (pin "3") (pinfunction "3_3") (pintype "passive"))
      (node (ref "SHIFT_0") (pin "11") (pinfunction "SRCLK_11") (pintype "input"))
      (node (ref "SHIFT_1") (pin "11") (pinfunction "SRCLK_11") (pintype "input"))
      (node (ref "U$1") (pin "SCK5") (pinfunction "SCLK_SCK5") (pintype "input"))
      (node (ref "U1") (pin "17") (pinfunction "PB5(SCK)_17") (pintype "bidirectional"))
    )
    (net (code "138") (name "/SCL") (class "Default")
      (node (ref "DS3231M") (pin "8") (pinfunction "P$8_SCL_8") (pintype "bidirectional"))
      (node (ref "OLED") (pin "3") (pinfunction "3_3") (pintype "passive"))
      (node (ref "R7") (pin "1") (pinfunction "1_1") (pintype "passive"))
      (node (ref "U1") (pin "28") (pinfunction "PC5(ADC5/SCL)_28") (pintype "bidirectional"))
    )
    (net (code "139") (name "/SDA") (class "Default")
      (node (ref "DS3231M") (pin "7") (pinfunction "P$7_SDA_7") (pintype "bidirectional"))
      (node (ref "OLED") (pin "4") (pinfunction "4_4") (pintype "passive"))
      (node (ref "R8") (pin "1") (pinfunction "1_1") (pintype "passive"))
      (node (ref "U1") (pin "27") (pinfunction "PC4(ADC4/SDA)_27") (pintype "bidirectional"))
    )
    (net (code "140") (name "/SHIFT_CLEAR") (class "Default")
      (node (ref "R14") (pin "1") (pinfunction "1_1") (pintype "passive"))
      (node (ref "SHIFT_0") (pin "10") (pinfunction "~{SRCLR}_10") (pintype "input"))
      (node (ref "SHIFT_1") (pin "10") (pinfunction "~{SRCLR}_10") (pintype "input"))
      (node (ref "U1") (pin "24") (pinfunction "PC1(ADC1)_24") (pintype "bidirectional"))
    )
    (net (code "141") (name "/TO_FTDI_RX") (class "Default")
      (node (ref "JP1") (pin "5") (pinfunction "5_5") (pintype "passive"))
      (node (ref "U1") (pin "31") (pinfunction "PD1(TXD)_31") (pintype "bidirectional"))
    )
    (net (code "142") (name "/TO_FTDI_TX") (class "Default")
      (node (ref "JP1") (pin "4") (pinfunction "4_4") (pintype "passive"))
      (node (ref "U1") (pin "30") (pinfunction "PD0(RXD)_30") (pintype "bidirectional"))
    )
    (net (code "143") (name "/VBAT") (class "Default")
      (node (ref "CR1220_BATTERY") (pin "P$1") (pinfunction "VBAT_P$1") (pintype "power_in"))
      (node (ref "CR1220_BATTERY") (pin "P$2") (pinfunction "P$2_P$2") (pintype "power_in"))
      (node (ref "DS3231M") (pin "6") (pinfunction "P$6_VBAT_6") (pintype "bidirectional"))
    )
    (net (code "144") (name "/VBATTERY") (class "Default")
      (node (ref "LTC4411") (pin "1") (pinfunction "VIN_1") (pintype "passive"))
      (node (ref "MOLEX_KK") (pin "2") (pinfunction "S_2") (pintype "passive"))
      (node (ref "PRIMARY_BATTERY") (pin "VBAT") (pinfunction "VBAT_VBAT") (pintype "power_in"))
    )
    (net (code "145") (name "/VRAW") (class "Default")
      (node (ref "P-FET") (pin "2") (pinfunction "S_2") (pintype "passive"))
      (node (ref "R33") (pin "2") (pinfunction "2_2") (pintype "passive"))
    )
    (net (code "146") (name "/VRAW1") (class "Default")
      (node (ref "C25") (pin "1") (pinfunction "1_1") (pintype "passive"))
      (node (ref "LTC4411") (pin "5") (pinfunction "OUT_5") (pintype "passive"))
      (node (ref "PWR_JUMPER") (pin "2") (pinfunction "2_2") (pintype "passive"))
      (node (ref "PWR_PASSTHRU") (pin "2") (pinfunction "P$2_2") (pintype "bidirectional"))
      (node (ref "SCHOTTKY") (pin "C") (pinfunction "C_C") (pintype "passive"))
    )
    (net (code "147") (name "/VRAW2") (class "Default")
      (node (ref "C1") (pin "+") (pinfunction "+_+") (pintype "passive"))
      (node (ref "MCP1700T-3302") (pin "3") (pinfunction "VIN_3") (pintype "input"))
      (node (ref "PWR_JUMPER") (pin "1") (pinfunction "1_1") (pintype "passive"))
      (node (ref "PWR_PASSTHRU") (pin "1") (pinfunction "P$1_1") (pintype "bidirectional"))
    )
    (net (code "148") (name "/V_JACK") (class "Default")
      (node (ref "2,1MM_JACK") (pin "P$1") (pinfunction "PWR_P$1") (pintype "bidirectional"))
      (node (ref "SCHOTTKY") (pin "A") (pinfunction "A_A") (pintype "passive"))
    )
    (net (code "149") (name "/~{SLEEP0}") (class "Default")
      (node (ref "A139_HALL0") (pin "P$5") (pinfunction "P$5_P$5") (pintype "bidirectional"))
      (node (ref "R50") (pin "2") (pinfunction "2_2") (pintype "passive"))
    )
    (net (code "150") (name "/~{SLEEP1}") (class "Default")
      (node (ref "A139_HALL1") (pin "P$5") (pinfunction "P$5_P$5") (pintype "bidirectional"))
      (node (ref "R51") (pin "2") (pinfunction "2_2") (pintype "passive"))
    )
    (net (code "151") (name "/~{SLEEP2}") (class "Default")
      (node (ref "A139_HALL2") (pin "P$5") (pinfunction "P$5_P$5") (pintype "bidirectional"))
      (node (ref "R52") (pin "2") (pinfunction "2_2") (pintype "passive"))
    )
    (net (code "152") (name "/~{SLEEP3}") (class "Default")
      (node (ref "A139_HALL3") (pin "P$5") (pinfunction "P$5_P$5") (pintype "bidirectional"))
      (node (ref "R53") (pin "2") (pinfunction "2_2") (pintype "passive"))
    )
    (net (code "153") (name "/~{SLEEP4}") (class "Default")
      (node (ref "A139_HALL4") (pin "P$5") (pinfunction "P$5_P$5") (pintype "bidirectional"))
      (node (ref "R54") (pin "2") (pinfunction "2_2") (pintype "passive"))
    )
    (net (code "154") (name "/~{SLEEP5}") (class "Default")
      (node (ref "A139_HALL5") (pin "P$5") (pinfunction "P$5_P$5") (pintype "bidirectional"))
      (node (ref "R55") (pin "2") (pinfunction "2_2") (pintype "passive"))
    )
    (net (code "155") (name "/~{SLEEP6}") (class "Default")
      (node (ref "A139_HALL6") (pin "P$5") (pinfunction "P$5_P$5") (pintype "bidirectional"))
      (node (ref "R56") (pin "2") (pinfunction "2_2") (pintype "passive"))
    )
    (net (code "156") (name "/~{SLEEP7}") (class "Default")
      (node (ref "A139_HALL7") (pin "P$5") (pinfunction "P$5_P$5") (pintype "bidirectional"))
      (node (ref "R57") (pin "2") (pinfunction "2_2") (pintype "passive"))
    )
    (net (code "157") (name "/~{SLEEP8}") (class "Default")
      (node (ref "A139_HALL8") (pin "P$5") (pinfunction "P$5_P$5") (pintype "bidirectional"))
      (node (ref "R58") (pin "2") (pinfunction "2_2") (pintype "passive"))
    )
    (net (code "158") (name "/~{SLEEP9}") (class "Default")
      (node (ref "A139_HALL9") (pin "P$5") (pinfunction "P$5_P$5") (pintype "bidirectional"))
      (node (ref "R59") (pin "2") (pinfunction "2_2") (pintype "passive"))
    )
    (net (code "159") (name "/~{SLEEP10}") (class "Default")
      (node (ref "A139_HALL10") (pin "P$5") (pinfunction "P$5_P$5") (pintype "bidirectional"))
      (node (ref "R60") (pin "2") (pinfunction "2_2") (pintype "passive"))
    )
    (net (code "160") (name "/~{SLEEP11}") (class "Default")
      (node (ref "A139_HALL11") (pin "P$5") (pinfunction "P$5_P$5") (pintype "bidirectional"))
      (node (ref "R61") (pin "2") (pinfunction "2_2") (pintype "passive"))
    )
    (net (code "161") (name "/~{SLEEP12}") (class "Default")
      (node (ref "A139_HALL12") (pin "P$5") (pinfunction "P$5_P$5") (pintype "bidirectional"))
      (node (ref "R62") (pin "2") (pinfunction "2_2") (pintype "passive"))
    )
    (net (code "162") (name "/~{SLEEP13}") (class "Default")
      (node (ref "A139_HALL13") (pin "P$5") (pinfunction "P$5_P$5") (pintype "bidirectional"))
      (node (ref "R63") (pin "2") (pinfunction "2_2") (pintype "passive"))
    )
    (net (code "163") (name "/~{SLEEP14}") (class "Default")
      (node (ref "A139_HALL14") (pin "P$5") (pinfunction "P$5_P$5") (pintype "bidirectional"))
      (node (ref "R64") (pin "2") (pinfunction "2_2") (pintype "passive"))
    )
    (net (code "164") (name "/~{SLEEP15}") (class "Default")
      (node (ref "A139_HALL15") (pin "P$5") (pinfunction "P$5_P$5") (pintype "bidirectional"))
      (node (ref "R65") (pin "2") (pinfunction "2_2") (pintype "passive"))
    )
    (net (code "165") (name "/~{SLEEP16}") (class "Default")
      (node (ref "A139_HALL16") (pin "P$5") (pinfunction "P$5_P$5") (pintype "bidirectional"))
      (node (ref "R66") (pin "2") (pinfunction "2_2") (pintype "passive"))
    )
    (net (code "166") (name "/~{SLEEP17}") (class "Default")
      (node (ref "A139_HALL17") (pin "P$5") (pinfunction "P$5_P$5") (pintype "bidirectional"))
      (node (ref "R67") (pin "2") (pinfunction "2_2") (pintype "passive"))
    )
    (net (code "167") (name "/~{SLEEP18}") (class "Default")
      (node (ref "A139_HALL18") (pin "P$5") (pinfunction "P$5_P$5") (pintype "bidirectional"))
      (node (ref "R68") (pin "2") (pinfunction "2_2") (pintype "passive"))
    )
    (net (code "168") (name "/~{SLEEP19}") (class "Default")
      (node (ref "A139_HALL19") (pin "P$5") (pinfunction "P$5_P$5") (pintype "bidirectional"))
      (node (ref "R69") (pin "2") (pinfunction "2_2") (pintype "passive"))
    )
    (net (code "169") (name "GND") (class "Default")
      (node (ref "1") (pin "S$1") (pinfunction "S1_S$1") (pintype "passive"))
      (node (ref "2") (pin "S$1") (pinfunction "S1_S$1") (pintype "passive"))
      (node (ref "2,1MM_JACK") (pin "P$2") (pinfunction "GND_P$2") (pintype "bidirectional"))
      (node (ref "BJT") (pin "2") (pinfunction "E_2") (pintype "passive"))
      (node (ref "C1") (pin "-") (pinfunction "-_-") (pintype "passive"))
      (node (ref "C10") (pin "2") (pinfunction "2_2") (pintype "passive"))
      (node (ref "C2") (pin "-") (pinfunction "-_-") (pintype "passive"))
      (node (ref "C25") (pin "2") (pinfunction "2_2") (pintype "passive"))
      (node (ref "C3") (pin "2") (pinfunction "2_2") (pintype "passive"))
      (node (ref "C4") (pin "2") (pinfunction "2_2") (pintype "passive"))
      (node (ref "C6") (pin "2") (pinfunction "2_2") (pintype "passive"))
      (node (ref "C7") (pin "2") (pinfunction "2_2") (pintype "passive"))
      (node (ref "C8") (pin "2") (pinfunction "2_2") (pintype "passive"))
      (node (ref "C9") (pin "2") (pinfunction "2_2") (pintype "passive"))
      (node (ref "CR1220_BATTERY") (pin "GND") (pinfunction "GND_GND") (pintype "power_in"))
      (node (ref "DS3231M") (pin "5") (pinfunction "P$5_GND_5") (pintype "power_in"))
      (node (ref "GND") (pin "1") (pinfunction "P$1_1") (pintype "bidirectional"))
      (node (ref "GROUND_CON") (pin "1") (pinfunction "P$1_1") (pintype "bidirectional"))
      (node (ref "J1") (pin "6") (pinfunction "6_6") (pintype "passive"))
      (node (ref "JP1") (pin "1") (pinfunction "1_1") (pintype "passive"))
      (node (ref "JP1") (pin "2") (pinfunction "2_2") (pintype "passive"))
      (node (ref "LED1") (pin "C") (pinfunction "C_C") (pintype "passive"))
      (node (ref "LED2") (pin "C") (pinfunction "C_C") (pintype "passive"))
      (node (ref "LTC4411") (pin "2") (pinfunction "GND_2") (pintype "passive"))
      (node (ref "LTC4411") (pin "3") (pinfunction "CTL_3") (pintype "passive"))
      (node (ref "MCP1700T-3302") (pin "1") (pinfunction "GND_1") (pintype "passive"))
      (node (ref "MOLEX_KK") (pin "1") (pinfunction "S_1") (pintype "passive"))
      (node (ref "OLED") (pin "2") (pinfunction "2_2") (pintype "passive"))
      (node (ref "PRIMARY_BATTERY") (pin "GND") (pinfunction "GND_GND") (pintype "power_in"))
      (node (ref "R29") (pin "1") (pinfunction "1_1") (pintype "passive"))
      (node (ref "R3") (pin "1") (pinfunction "1_1") (pintype "passive"))
      (node (ref "R32") (pin "1") (pinfunction "1_1") (pintype "passive"))
      (node (ref "RESET") (pin "P$1") (pinfunction "P1_P$1") (pintype "passive"))
      (node (ref "SHIFT_0") (pin "13") (pinfunction "~{OE}_13") (pintype "input"))
      (node (ref "SHIFT_0") (pin "8") (pinfunction "GND_8") (pintype "power_in"))
      (node (ref "SHIFT_1") (pin "13") (pinfunction "~{OE}_13") (pintype "input"))
      (node (ref "SHIFT_1") (pin "8") (pinfunction "GND_8") (pintype "power_in"))
      (node (ref "U$1") (pin "GND6") (pinfunction "VSS_GND_GND6") (pintype "power_in"))
      (node (ref "U$1") (pin "MNT1") (pinfunction "GND1_MNT1") (pintype "power_in"))
      (node (ref "U$1") (pin "MNT2") (pinfunction "GND2_MNT2") (pintype "power_in"))
      (node (ref "U$1") (pin "MNT3") (pinfunction "GND3_MNT3") (pintype "power_in"))
      (node (ref "U$1") (pin "MNT4") (pinfunction "GND4_MNT4") (pintype "power_in"))
      (node (ref "U$2") (pin "12") (pinfunction "GND_12") (pintype "power_in"))
      (node (ref "U$4") (pin "1") (pinfunction "P$1_1") (pintype "bidirectional"))
      (node (ref "U$7") (pin "1") (pinfunction "P$1_1") (pintype "bidirectional"))
      (node (ref "U$9") (pin "1") (pinfunction "P$1_1") (pintype "bidirectional"))
      (node (ref "U1") (pin "3") (pinfunction "GND_3") (pintype "bidirectional"))
      (node (ref "U1") (pin "5") (pinfunction "GND_5") (pintype "bidirectional"))
    )
    (net (code "170") (name "Net-(BJT-B)") (class "Default")
      (node (ref "BJT") (pin "1") (pinfunction "B_1") (pintype "passive"))
      (node (ref "R31") (pin "2") (pinfunction "2_2") (pintype "passive"))
    )
    (net (code "171") (name "Net-(LED1-PadA)") (class "Default")
      (node (ref "LED1") (pin "A") (pinfunction "A_A") (pintype "passive"))
      (node (ref "R1") (pin "1") (pinfunction "1_1") (pintype "passive"))
    )
    (net (code "172") (name "Net-(LED2-PadA)") (class "Default")
      (node (ref "LED2") (pin "A") (pinfunction "A_A") (pintype "passive"))
      (node (ref "R2") (pin "1") (pinfunction "1_1") (pintype "passive"))
    )
    (net (code "173") (name "Net-(LTC4411-STAT)") (class "Default")
      (node (ref "LTC4411") (pin "4") (pinfunction "STAT_4") (pintype "passive"))
      (node (ref "R34") (pin "1") (pinfunction "1_1") (pintype "passive"))
    )
    (net (code "174") (name "Net-(P-FET-D)") (class "Default")
      (node (ref "P-FET") (pin "3") (pinfunction "D_3") (pintype "passive"))
      (node (ref "R30") (pin "2") (pinfunction "2_2") (pintype "passive"))
    )
    (net (code "175") (name "Net-(SHIFT_0-QH*)") (class "Default")
      (node (ref "SHIFT_0") (pin "9") (pinfunction "QH*_9") (pintype "tri_state"))
      (node (ref "SHIFT_1") (pin "14") (pinfunction "SER_14") (pintype "input"))
    )
    (net (code "176") (name "Net-(U$1-DAT1_NC)") (class "Default")
      (node (ref "R5") (pin "1") (pinfunction "1_1") (pintype "passive"))
      (node (ref "U$1") (pin "NC1") (pinfunction "DAT1_NC_NC1") (pintype "bidirectional"))
    )
    (net (code "177") (name "Net-(U$1-DAT2_RES)") (class "Default")
      (node (ref "R4") (pin "1") (pinfunction "1_1") (pintype "passive"))
      (node (ref "U$1") (pin "RES8") (pinfunction "DAT2_RES_RES8") (pintype "bidirectional"))
    )
    (net (code "178") (name "VCC") (class "Default")
      (node (ref "C10") (pin "1") (pinfunction "1_1") (pintype "passive"))
      (node (ref "C2") (pin "+") (pinfunction "+_+") (pintype "passive"))
      (node (ref "C3") (pin "1") (pinfunction "1_1") (pintype "passive"))
      (node (ref "C4") (pin "1") (pinfunction "1_1") (pintype "passive"))
      (node (ref "C6") (pin "1") (pinfunction "1_1") (pintype "passive"))
      (node (ref "C7") (pin "1") (pinfunction "1_1") (pintype "passive"))
      (node (ref "C8") (pin "1") (pinfunction "1_1") (pintype "passive"))
      (node (ref "C9") (pin "1") (pinfunction "1_1") (pintype "passive"))
      (node (ref "DS3231M") (pin "2") (pinfunction "P$2_VCC_2") (pintype "power_in"))
      (node (ref "HALL0") (pin "1") (pinfunction "1_1") (pintype "passive"))
      (node (ref "HALL1") (pin "1") (pinfunction "1_1") (pintype "passive"))
      (node (ref "HALL10") (pin "1") (pinfunction "1_1") (pintype "passive"))
      (node (ref "HALL11") (pin "1") (pinfunction "1_1") (pintype "passive"))
      (node (ref "HALL12") (pin "1") (pinfunction "1_1") (pintype "passive"))
      (node (ref "HALL13") (pin "1") (pinfunction "1_1") (pintype "passive"))
      (node (ref "HALL14") (pin "1") (pinfunction "1_1") (pintype "passive"))
      (node (ref "HALL15") (pin "1") (pinfunction "1_1") (pintype "passive"))
      (node (ref "HALL2") (pin "1") (pinfunction "1_1") (pintype "passive"))
      (node (ref "HALL3") (pin "1") (pinfunction "1_1") (pintype "passive"))
      (node (ref "HALL4") (pin "1") (pinfunction "1_1") (pintype "passive"))
      (node (ref "HALL5") (pin "1") (pinfunction "1_1") (pintype "passive"))
      (node (ref "HALL6") (pin "1") (pinfunction "1_1") (pintype "passive"))
      (node (ref "HALL7") (pin "1") (pinfunction "1_1") (pintype "passive"))
      (node (ref "HALL8") (pin "1") (pinfunction "1_1") (pintype "passive"))
      (node (ref "HALL9") (pin "1") (pinfunction "1_1") (pintype "passive"))
      (node (ref "INDUCTOR") (pin "P$2") (pinfunction "2_P$2") (pintype "passive"))
      (node (ref "J1") (pin "2") (pinfunction "2_2") (pintype "passive"))
      (node (ref "JP1") (pin "3") (pinfunction "3_3") (pintype "passive"))
      (node (ref "MCP1700T-3302") (pin "2") (pinfunction "VOUT_2") (pintype "output"))
      (node (ref "OLED") (pin "1") (pinfunction "1_1") (pintype "passive"))
      (node (ref "R14") (pin "2") (pinfunction "2_2") (pintype "passive"))
      (node (ref "R15") (pin "2") (pinfunction "2_2") (pintype "passive"))
      (node (ref "R28") (pin "2") (pinfunction "2_2") (pintype "passive"))
      (node (ref "R34") (pin "2") (pinfunction "2_2") (pintype "passive"))
      (node (ref "R4") (pin "2") (pinfunction "2_2") (pintype "passive"))
      (node (ref "R5") (pin "2") (pinfunction "2_2") (pintype "passive"))
      (node (ref "R6") (pin "2") (pinfunction "2_2") (pintype "passive"))
      (node (ref "R7") (pin "2") (pinfunction "2_2") (pintype "passive"))
      (node (ref "R8") (pin "2") (pinfunction "2_2") (pintype "passive"))
      (node (ref "R9") (pin "2") (pinfunction "2_2") (pintype "passive"))
      (node (ref "SHIFT_0") (pin "16") (pinfunction "VCC_16") (pintype "power_in"))
      (node (ref "SHIFT_1") (pin "16") (pinfunction "VCC_16") (pintype "power_in"))
      (node (ref "U$1") (pin "VDD4") (pinfunction "VDD_VDD4") (pintype "power_in"))
      (node (ref "U$2") (pin "24") (pinfunction "VCC_24") (pintype "power_in"))
      (node (ref "U1") (pin "4") (pinfunction "VCC_4") (pintype "bidirectional"))
      (node (ref "U1") (pin "6") (pinfunction "VCC_6") (pintype "bidirectional"))
    )
    (net (code "179") (name "unconnected-(1-PadP)") (class "Default")
      (node (ref "1") (pin "P") (pinfunction "P_P") (pintype "passive"))
    )
    (net (code "180") (name "unconnected-(1-PadS)") (class "Default")
      (node (ref "1") (pin "S") (pinfunction "S_S") (pintype "passive"))
    )
    (net (code "181") (name "unconnected-(2,1MM_JACK-GNDBREAK-PadP$3)") (class "Default")
      (node (ref "2,1MM_JACK") (pin "P$3") (pinfunction "GNDBREAK_P$3") (pintype "bidirectional"))
    )
    (net (code "182") (name "unconnected-(2-PadP)") (class "Default")
      (node (ref "2") (pin "P") (pinfunction "P_P") (pintype "passive"))
    )
    (net (code "183") (name "unconnected-(2-PadS)") (class "Default")
      (node (ref "2") (pin "S") (pinfunction "S_S") (pintype "passive"))
    )
    (net (code "184") (name "unconnected-(DS3231M-P$3_INT-Pad3)") (class "Default")
      (node (ref "DS3231M") (pin "3") (pinfunction "P$3_INT_3") (pintype "bidirectional"))
    )
    (net (code "185") (name "unconnected-(DS3231M-P$4_RST-Pad4)") (class "Default")
      (node (ref "DS3231M") (pin "4") (pinfunction "P$4_RST_4") (pintype "bidirectional"))
    )
    (net (code "186") (name "unconnected-(RESET-PadP)") (class "Default")
      (node (ref "RESET") (pin "P") (pinfunction "P_P") (pintype "passive"))
    )
    (net (code "187") (name "unconnected-(RESET-PadS)") (class "Default")
      (node (ref "RESET") (pin "S") (pinfunction "S_S") (pintype "passive"))
    )
    (net (code "188") (name "unconnected-(SHIFT_1-QH*-Pad9)") (class "Default")
      (node (ref "SHIFT_1") (pin "9") (pinfunction "QH*_9") (pintype "tri_state"))
    )
    (net (code "189") (name "unconnected-(U$1-CARD_DETECT-PadCARD_DETECT1)") (class "Default")
      (node (ref "U$1") (pin "CARD_DETECT1") (pinfunction "CARD_DETECT_CARD_DETECT1") (pintype "passive"))
    )
    (net (code "190") (name "unconnected-(U$1-CARD_DETECT1-PadCARD_DETECT2)") (class "Default")
      (node (ref "U$1") (pin "CARD_DETECT2") (pinfunction "CARD_DETECT1_CARD_DETECT2") (pintype "passive"))
    )
  )
)
